# v7-flex2811_32x.net
KiCad netlist of a schematic drawn in EAGLE
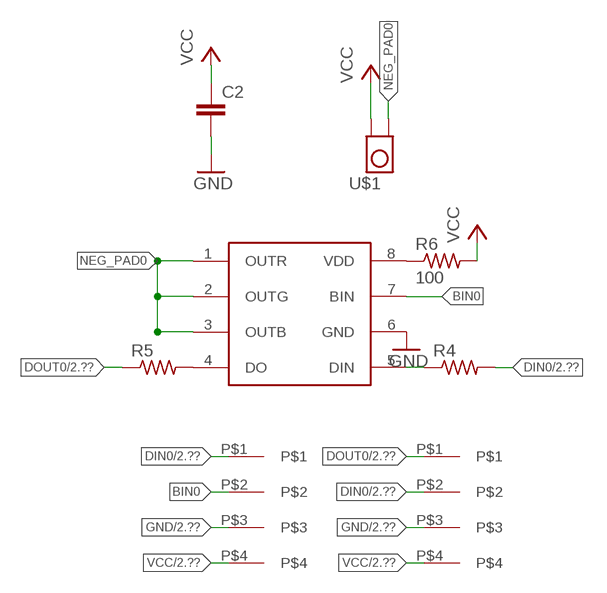
[diagram p0: schematic, sheet 1]
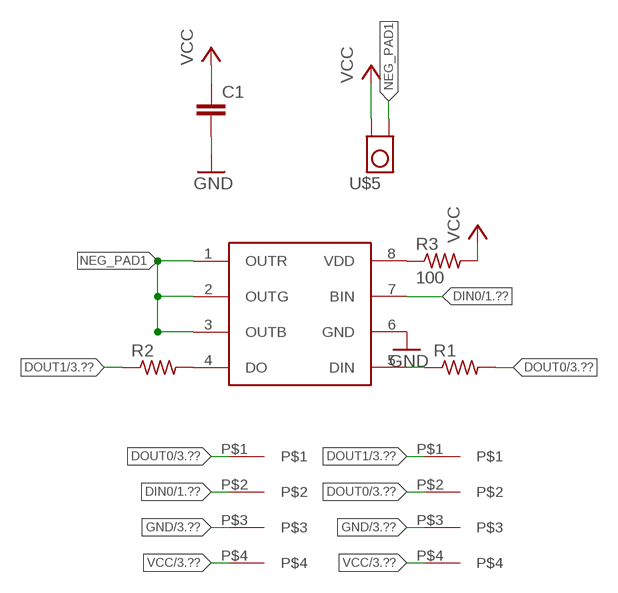
[diagram p1: schematic, sheet 2]
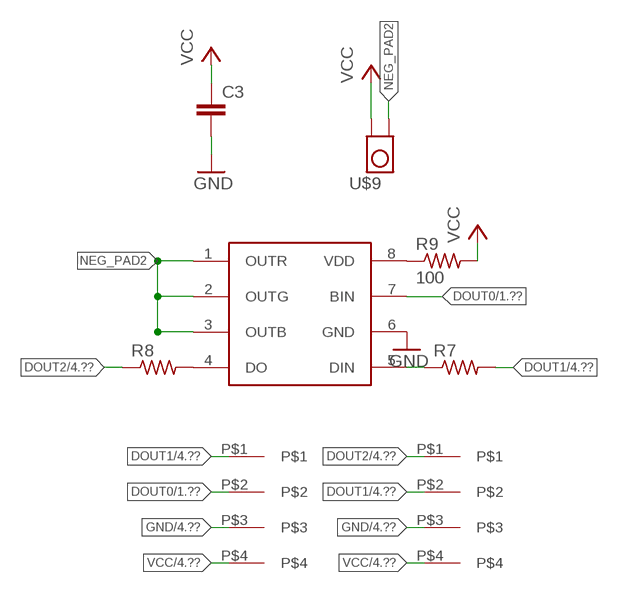
[diagram p2: schematic, sheet 3]
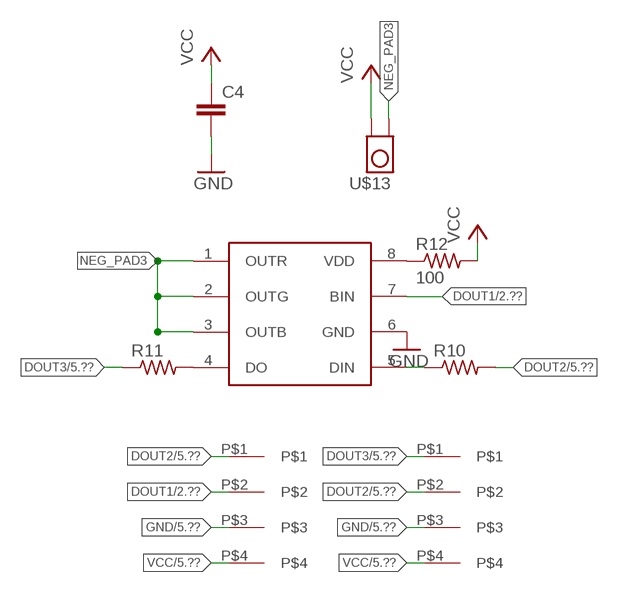
[diagram p3: schematic, sheet 4]
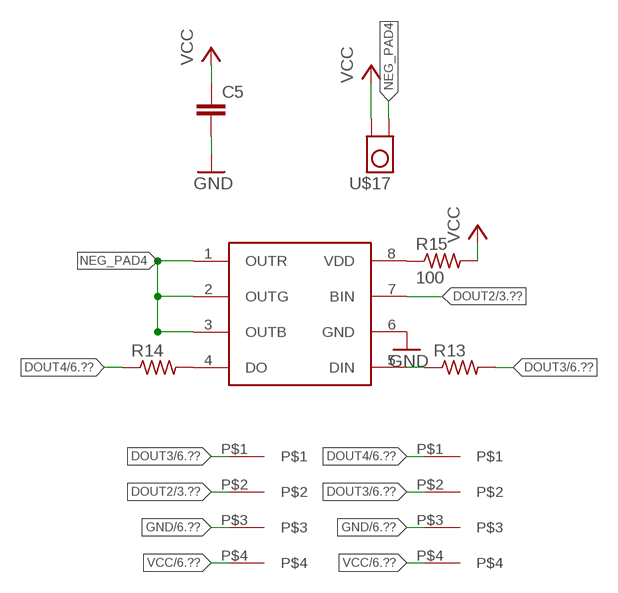
[diagram p4: schematic, sheet 5]
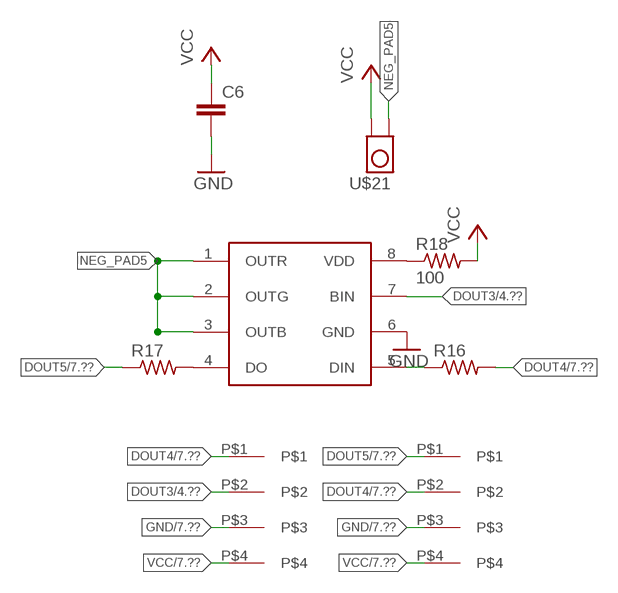
[diagram p5: schematic, sheet 6]
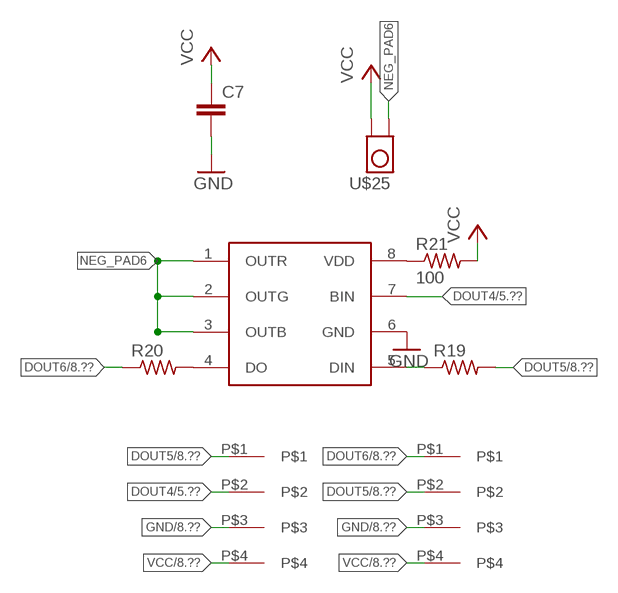
[diagram p6: schematic, sheet 7]
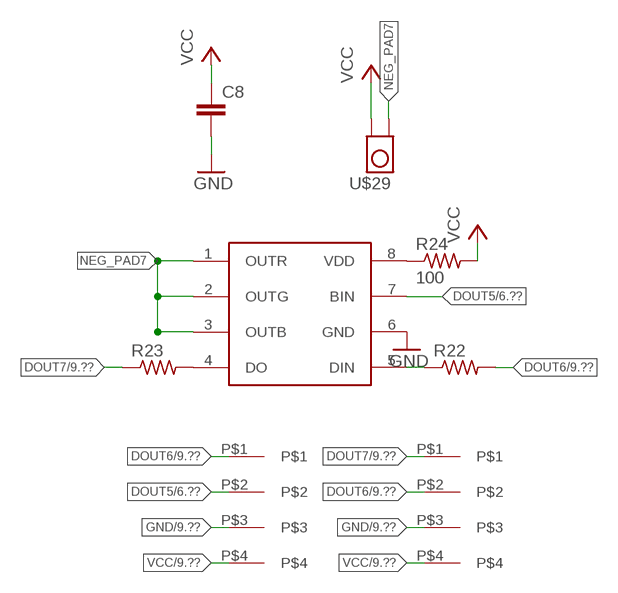
[diagram p7: schematic, sheet 8]
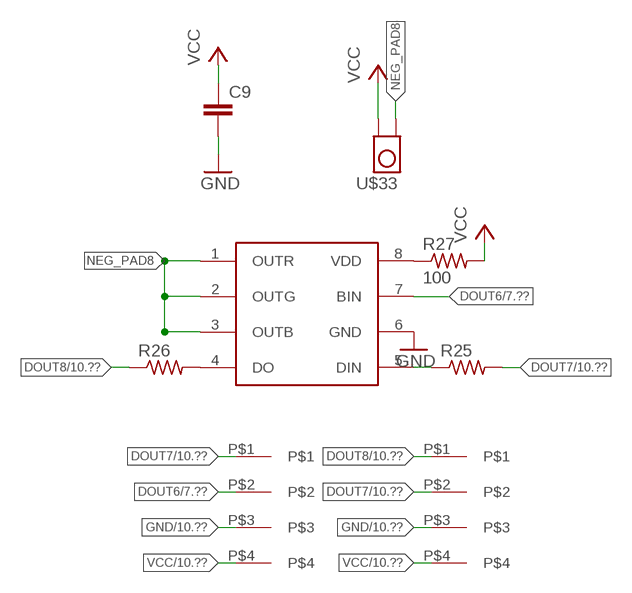
[diagram p8: schematic, sheet 9]
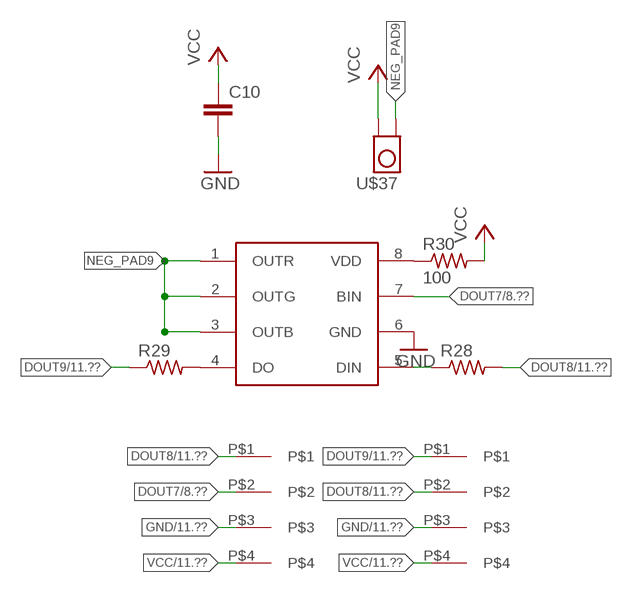
[diagram p9: schematic, sheet 10]
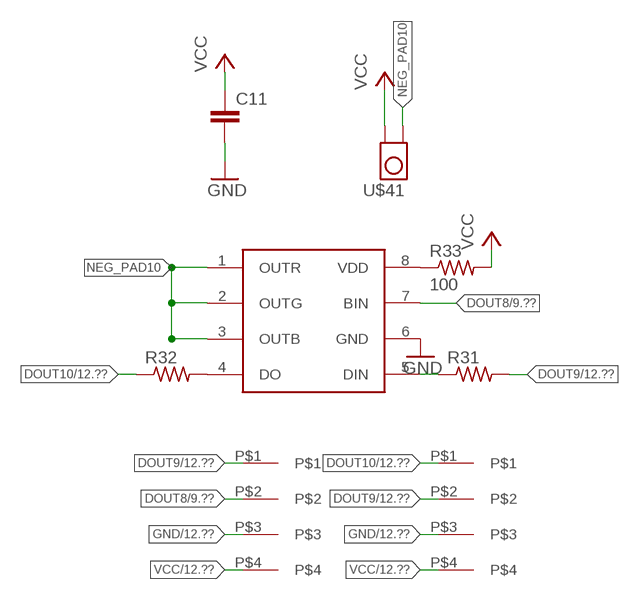
[diagram p10: schematic, sheet 11]
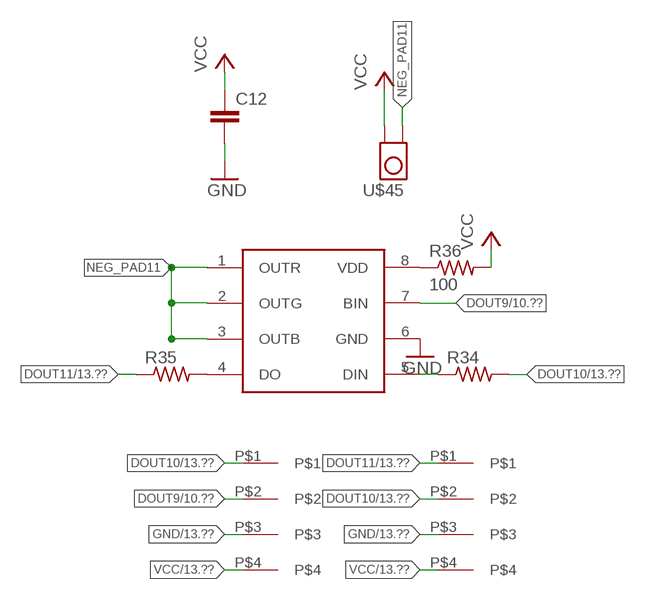
[diagram p11: schematic, sheet 12]
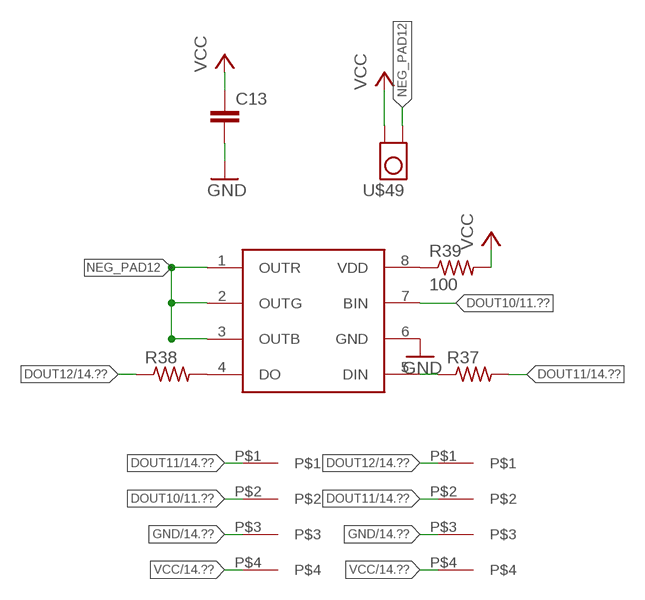
[diagram p12: schematic, sheet 13]
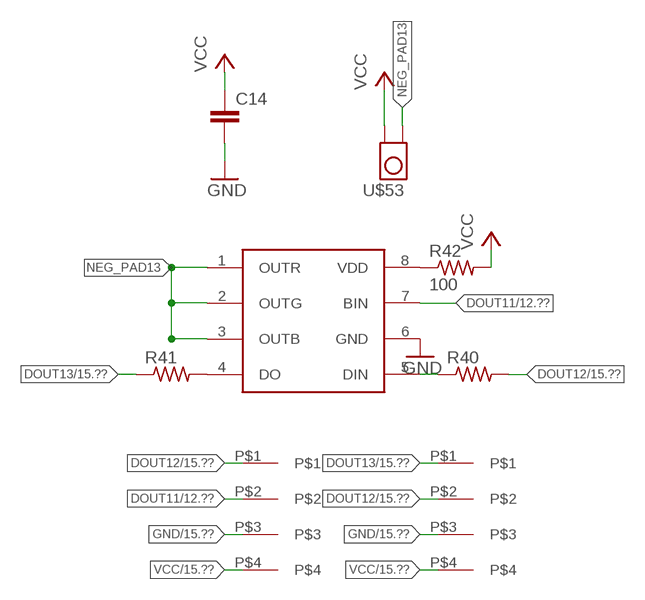
[diagram p13: schematic, sheet 14]
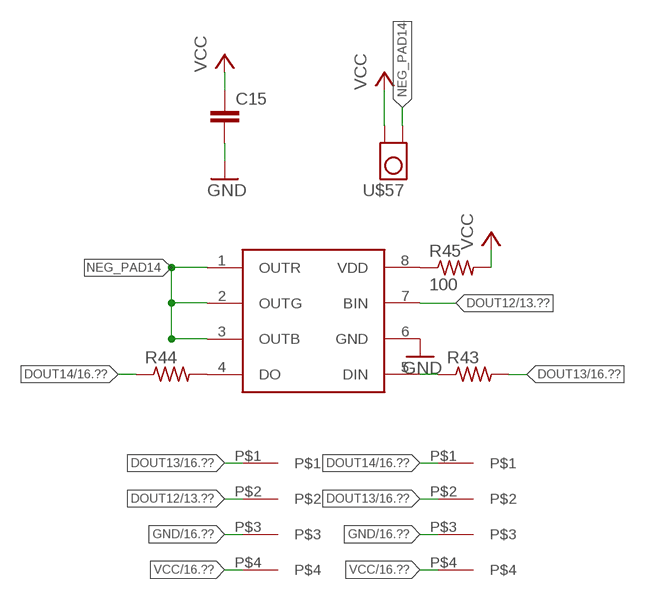
[diagram p14: schematic, sheet 15]
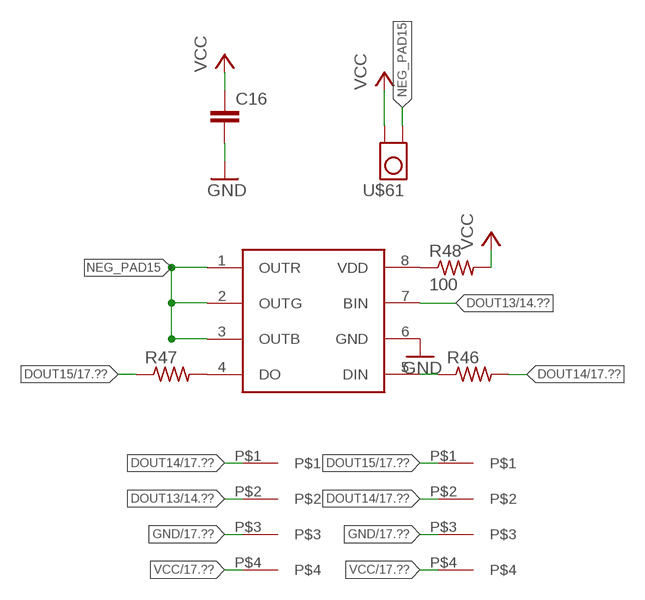
[diagram p15: schematic, sheet 16]
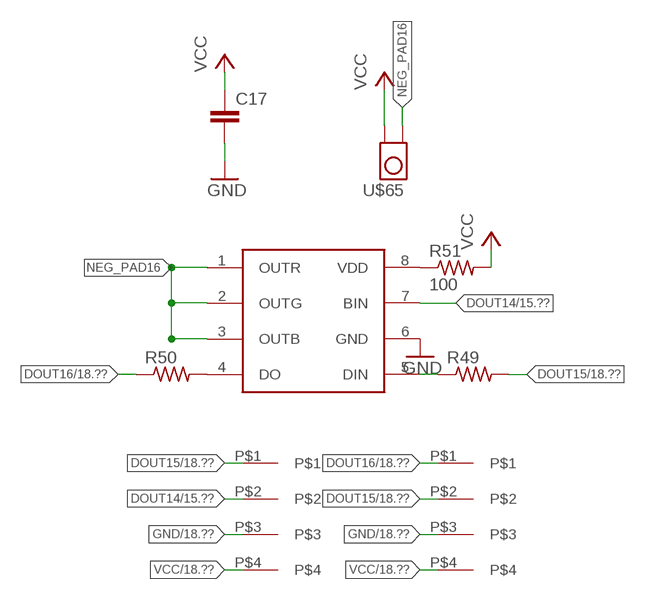
[diagram p16: schematic, sheet 17]
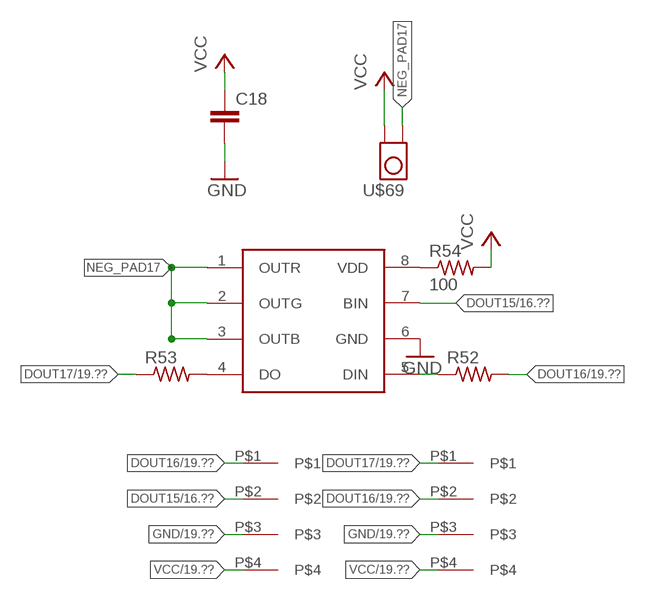
[diagram p17: schematic, sheet 18]
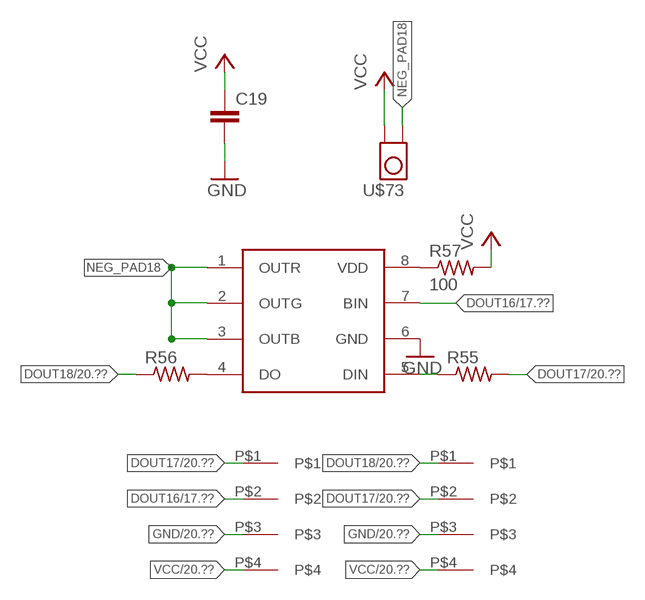
[diagram p18: schematic, sheet 19]
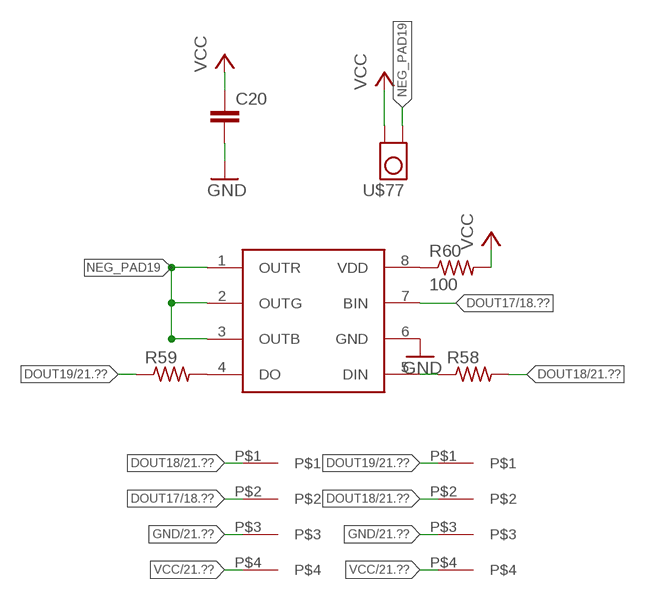
[diagram p19: schematic, sheet 20]
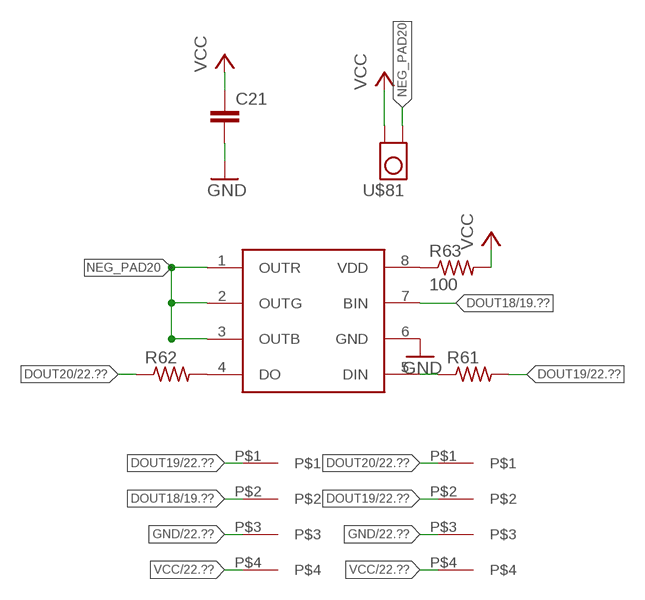
[diagram p20: schematic, sheet 21]
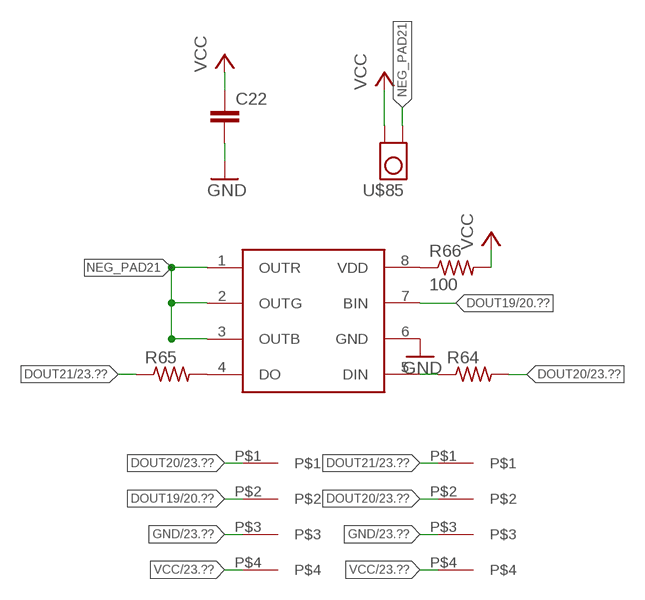
[diagram p21: schematic, sheet 22]
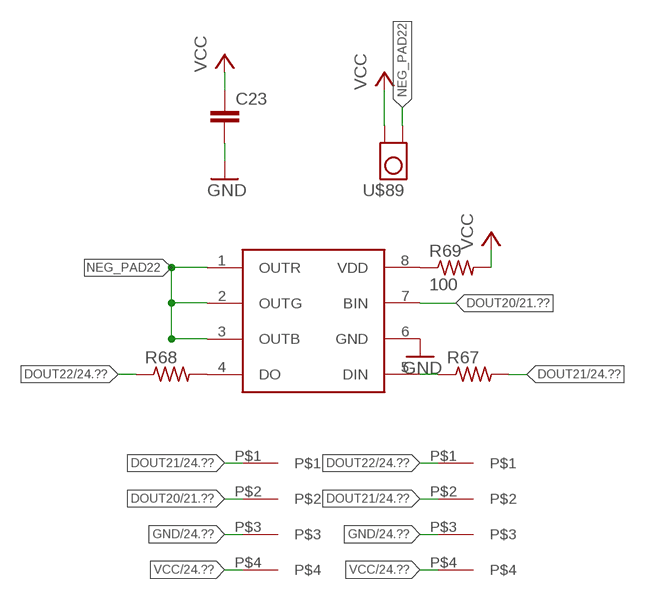
[diagram p22: schematic, sheet 23]
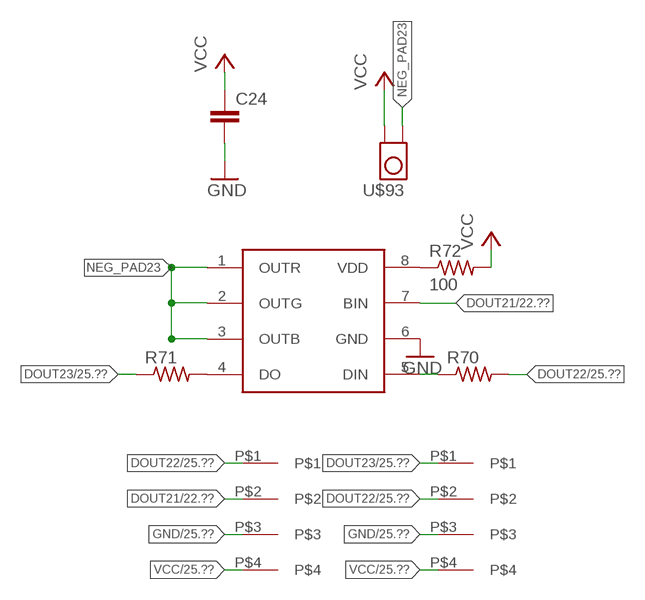
[diagram p23: schematic, sheet 24]
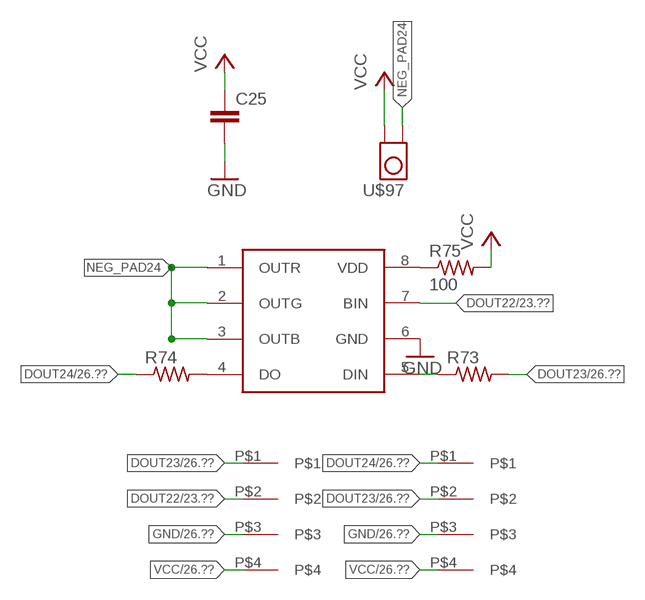
[diagram p24: schematic, sheet 25]
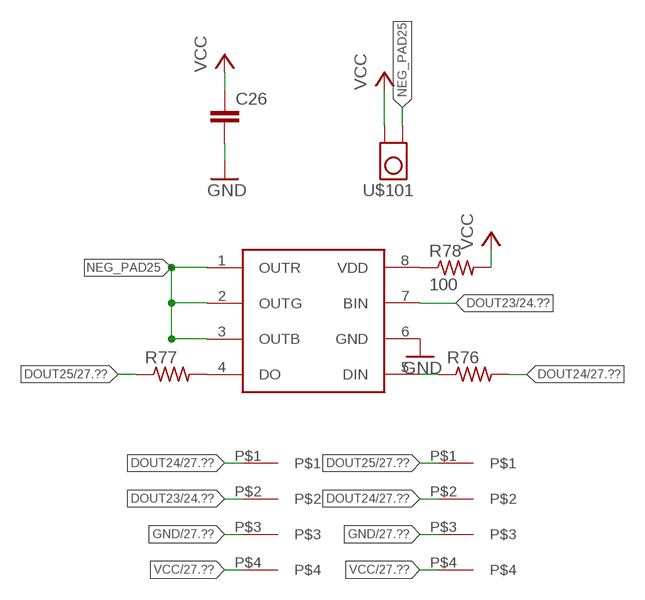
[diagram p25: schematic, sheet 26]
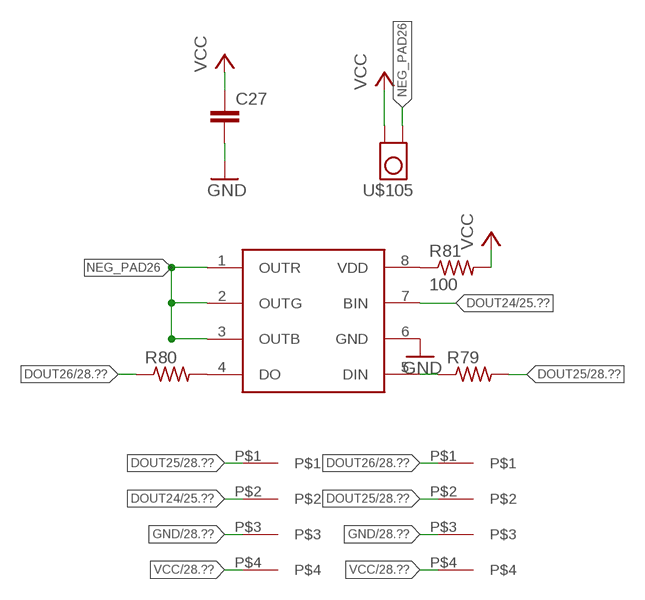
[diagram p26: schematic, sheet 27]
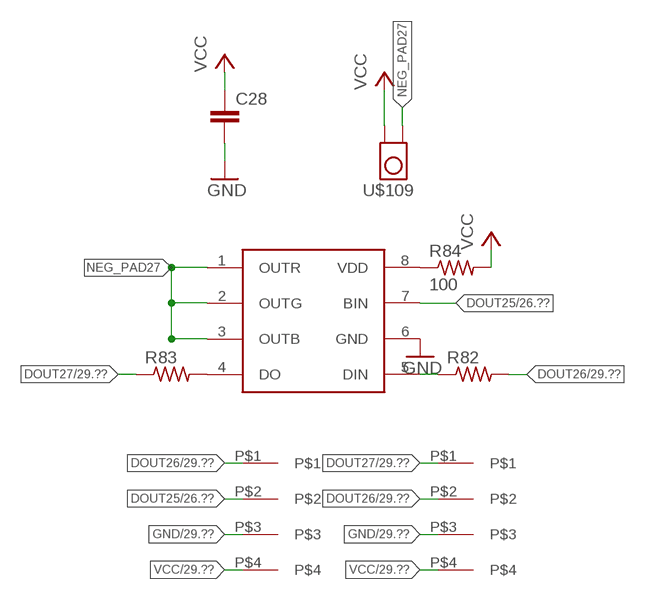
[diagram p27: schematic, sheet 28]
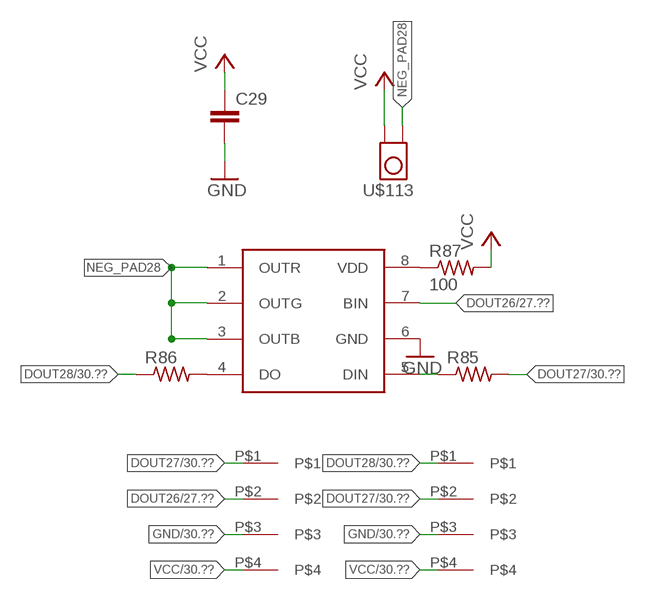
[diagram p28: schematic, sheet 29]
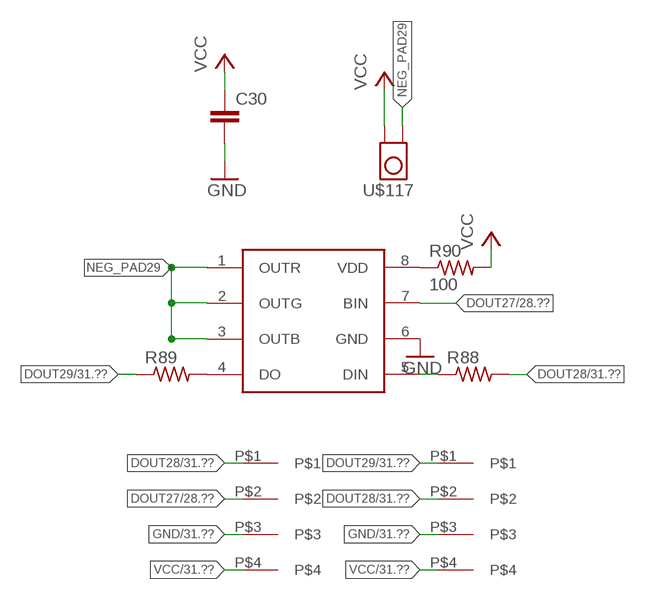
[diagram p29: schematic, sheet 30]
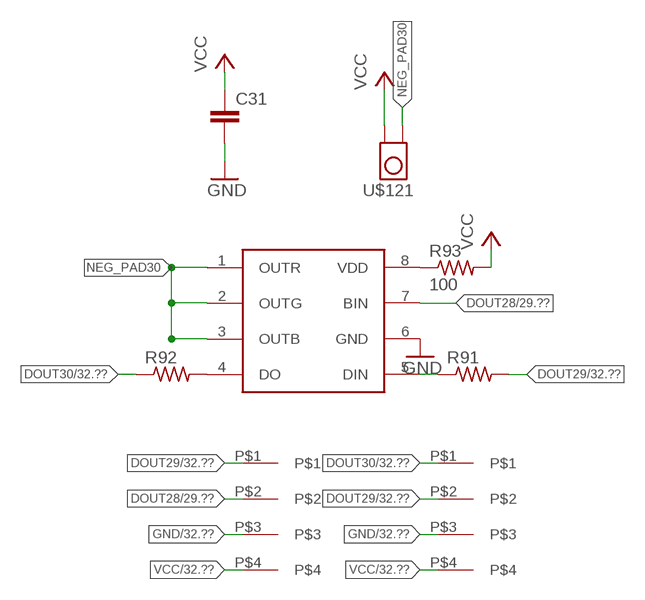
[diagram p30: schematic, sheet 31]
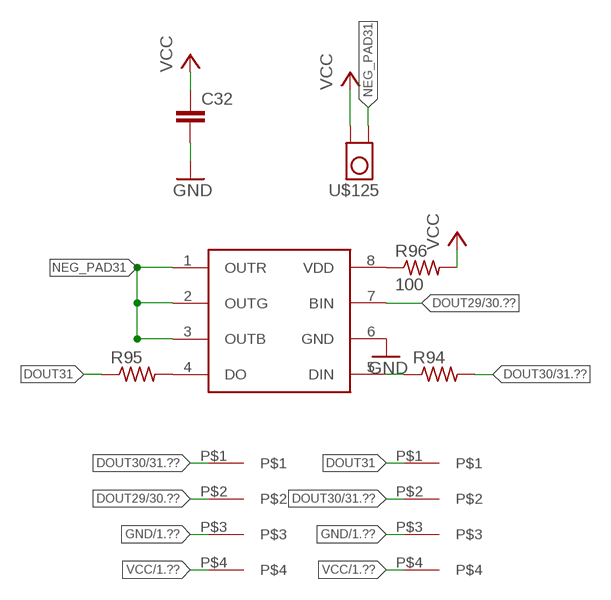
[diagram p31: schematic, sheet 32]

(export (version "E")
  (design (tool "Eeschema 10.0.6"))
  (components
    (comp (ref "C19")
      (value "C-EUC0201")
      (footprint "eagle-import:C0201")
      (libsource (lib "eagle-import") (part "C-EUC0201"))
    )
    (comp (ref "R55")
      (value "R-US_R0201")
      (footprint "eagle-import:R0201")
      (libsource (lib "eagle-import") (part "R-US_R0201"))
    )
    (comp (ref "R56")
      (value "R-US_R0201")
      (footprint "eagle-import:R0201")
      (libsource (lib "eagle-import") (part "R-US_R0201"))
    )
    (comp (ref "R57")
      (value "100")
      (footprint "eagle-import:R0201")
      (libsource (lib "eagle-import") (part "R-US_R0201"))
    )
    (comp (ref "U$73")
      (value "TP_4MM_MED_PAD")
      (footprint "eagle-import:TP_4MM_MED_PAD")
      (libsource (lib "eagle-import") (part "TP_4MM_MED_PAD"))
    )
    (comp (ref "U$75")
      (value "4PAD")
      (footprint "eagle-import:4PAD")
      (libsource (lib "eagle-import") (part "4PAD"))
    )
    (comp (ref "U$76")
      (value "4PAD")
      (footprint "eagle-import:4PAD")
      (libsource (lib "eagle-import") (part "4PAD"))
    )
    (comp (ref "U19")
      (value "WS2818")
      (footprint "eagle-import:SO08")
      (libsource (lib "eagle-import") (part "WS2818"))
    )
    (comp (ref "C20")
      (value "C-EUC0201")
      (footprint "eagle-import:C0201")
      (libsource (lib "eagle-import") (part "C-EUC0201"))
    )
    (comp (ref "R58")
      (value "R-US_R0201")
      (footprint "eagle-import:R0201")
      (libsource (lib "eagle-import") (part "R-US_R0201"))
    )
    (comp (ref "R59")
      (value "R-US_R0201")
      (footprint "eagle-import:R0201")
      (libsource (lib "eagle-import") (part "R-US_R0201"))
    )
    (comp (ref "R60")
      (value "100")
      (footprint "eagle-import:R0201")
      (libsource (lib "eagle-import") (part "R-US_R0201"))
    )
    (comp (ref "U$77")
      (value "TP_4MM_MED_PAD")
      (footprint "eagle-import:TP_4MM_MED_PAD")
      (libsource (lib "eagle-import") (part "TP_4MM_MED_PAD"))
    )
    (comp (ref "U$79")
      (value "4PAD")
      (footprint "eagle-import:4PAD")
      (libsource (lib "eagle-import") (part "4PAD"))
    )
    (comp (ref "U$80")
      (value "4PAD")
      (footprint "eagle-import:4PAD")
      (libsource (lib "eagle-import") (part "4PAD"))
    )
    (comp (ref "U20")
      (value "WS2818")
      (footprint "eagle-import:SO08")
      (libsource (lib "eagle-import") (part "WS2818"))
    )
    (comp (ref "C11")
      (value "C-EUC0201")
      (footprint "eagle-import:C0201")
      (libsource (lib "eagle-import") (part "C-EUC0201"))
    )
    (comp (ref "R31")
      (value "R-US_R0201")
      (footprint "eagle-import:R0201")
      (libsource (lib "eagle-import") (part "R-US_R0201"))
    )
    (comp (ref "R32")
      (value "R-US_R0201")
      (footprint "eagle-import:R0201")
      (libsource (lib "eagle-import") (part "R-US_R0201"))
    )
    (comp (ref "R33")
      (value "100")
      (footprint "eagle-import:R0201")
      (libsource (lib "eagle-import") (part "R-US_R0201"))
    )
    (comp (ref "U$41")
      (value "TP_4MM_MED_PAD")
      (footprint "eagle-import:TP_4MM_MED_PAD")
      (libsource (lib "eagle-import") (part "TP_4MM_MED_PAD"))
    )
    (comp (ref "U$43")
      (value "4PAD")
      (footprint "eagle-import:4PAD")
      (libsource (lib "eagle-import") (part "4PAD"))
    )
    (comp (ref "U$44")
      (value "4PAD")
      (footprint "eagle-import:4PAD")
      (libsource (lib "eagle-import") (part "4PAD"))
    )
    (comp (ref "U11")
      (value "WS2818")
      (footprint "eagle-import:SO08")
      (libsource (lib "eagle-import") (part "WS2818"))
    )
    (comp (ref "C17")
      (value "C-EUC0201")
      (footprint "eagle-import:C0201")
      (libsource (lib "eagle-import") (part "C-EUC0201"))
    )
    (comp (ref "R49")
      (value "R-US_R0201")
      (footprint "eagle-import:R0201")
      (libsource (lib "eagle-import") (part "R-US_R0201"))
    )
    (comp (ref "R50")
      (value "R-US_R0201")
      (footprint "eagle-import:R0201")
      (libsource (lib "eagle-import") (part "R-US_R0201"))
    )
    (comp (ref "R51")
      (value "100")
      (footprint "eagle-import:R0201")
      (libsource (lib "eagle-import") (part "R-US_R0201"))
    )
    (comp (ref "U$65")
      (value "TP_4MM_MED_PAD")
      (footprint "eagle-import:TP_4MM_MED_PAD")
      (libsource (lib "eagle-import") (part "TP_4MM_MED_PAD"))
    )
    (comp (ref "U$67")
      (value "4PAD")
      (footprint "eagle-import:4PAD")
      (libsource (lib "eagle-import") (part "4PAD"))
    )
    (comp (ref "U$68")
      (value "4PAD")
      (footprint "eagle-import:4PAD")
      (libsource (lib "eagle-import") (part "4PAD"))
    )
    (comp (ref "U17")
      (value "WS2818")
      (footprint "eagle-import:SO08")
      (libsource (lib "eagle-import") (part "WS2818"))
    )
    (comp (ref "C8")
      (value "C-EUC0201")
      (footprint "eagle-import:C0201")
      (libsource (lib "eagle-import") (part "C-EUC0201"))
    )
    (comp (ref "R22")
      (value "R-US_R0201")
      (footprint "eagle-import:R0201")
      (libsource (lib "eagle-import") (part "R-US_R0201"))
    )
    (comp (ref "R23")
      (value "R-US_R0201")
      (footprint "eagle-import:R0201")
      (libsource (lib "eagle-import") (part "R-US_R0201"))
    )
    (comp (ref "R24")
      (value "100")
      (footprint "eagle-import:R0201")
      (libsource (lib "eagle-import") (part "R-US_R0201"))
    )
    (comp (ref "U$29")
      (value "TP_4MM_MED_PAD")
      (footprint "eagle-import:TP_4MM_MED_PAD")
      (libsource (lib "eagle-import") (part "TP_4MM_MED_PAD"))
    )
    (comp (ref "U$31")
      (value "4PAD")
      (footprint "eagle-import:4PAD")
      (libsource (lib "eagle-import") (part "4PAD"))
    )
    (comp (ref "U$32")
      (value "4PAD")
      (footprint "eagle-import:4PAD")
      (libsource (lib "eagle-import") (part "4PAD"))
    )
    (comp (ref "U8")
      (value "WS2818")
      (footprint "eagle-import:SO08")
      (libsource (lib "eagle-import") (part "WS2818"))
    )
    (comp (ref "C21")
      (value "C-EUC0201")
      (footprint "eagle-import:C0201")
      (libsource (lib "eagle-import") (part "C-EUC0201"))
    )
    (comp (ref "R61")
      (value "R-US_R0201")
      (footprint "eagle-import:R0201")
      (libsource (lib "eagle-import") (part "R-US_R0201"))
    )
    (comp (ref "R62")
      (value "R-US_R0201")
      (footprint "eagle-import:R0201")
      (libsource (lib "eagle-import") (part "R-US_R0201"))
    )
    (comp (ref "R63")
      (value "100")
      (footprint "eagle-import:R0201")
      (libsource (lib "eagle-import") (part "R-US_R0201"))
    )
    (comp (ref "U$81")
      (value "TP_4MM_MED_PAD")
      (footprint "eagle-import:TP_4MM_MED_PAD")
      (libsource (lib "eagle-import") (part "TP_4MM_MED_PAD"))
    )
    (comp (ref "U$83")
      (value "4PAD")
      (footprint "eagle-import:4PAD")
      (libsource (lib "eagle-import") (part "4PAD"))
    )
    (comp (ref "U$84")
      (value "4PAD")
      (footprint "eagle-import:4PAD")
      (libsource (lib "eagle-import") (part "4PAD"))
    )
    (comp (ref "U21")
      (value "WS2818")
      (footprint "eagle-import:SO08")
      (libsource (lib "eagle-import") (part "WS2818"))
    )
    (comp (ref "C3")
      (value "C-EUC0201")
      (footprint "eagle-import:C0201")
      (libsource (lib "eagle-import") (part "C-EUC0201"))
    )
    (comp (ref "R7")
      (value "R-US_R0201")
      (footprint "eagle-import:R0201")
      (libsource (lib "eagle-import") (part "R-US_R0201"))
    )
    (comp (ref "R8")
      (value "R-US_R0201")
      (footprint "eagle-import:R0201")
      (libsource (lib "eagle-import") (part "R-US_R0201"))
    )
    (comp (ref "R9")
      (value "100")
      (footprint "eagle-import:R0201")
      (libsource (lib "eagle-import") (part "R-US_R0201"))
    )
    (comp (ref "U$9")
      (value "TP_4MM_MED_PAD")
      (footprint "eagle-import:TP_4MM_MED_PAD")
      (libsource (lib "eagle-import") (part "TP_4MM_MED_PAD"))
    )
    (comp (ref "U$11")
      (value "4PAD")
      (footprint "eagle-import:4PAD")
      (libsource (lib "eagle-import") (part "4PAD"))
    )
    (comp (ref "U$12")
      (value "4PAD")
      (footprint "eagle-import:4PAD")
      (libsource (lib "eagle-import") (part "4PAD"))
    )
    (comp (ref "U3")
      (value "WS2818")
      (footprint "eagle-import:SO08")
      (libsource (lib "eagle-import") (part "WS2818"))
    )
    (comp (ref "C2")
      (value "C-EUC0201")
      (footprint "eagle-import:C0201")
      (libsource (lib "eagle-import") (part "C-EUC0201"))
    )
    (comp (ref "R4")
      (value "R-US_R0201")
      (footprint "eagle-import:R0201")
      (libsource (lib "eagle-import") (part "R-US_R0201"))
    )
    (comp (ref "R5")
      (value "R-US_R0201")
      (footprint "eagle-import:R0201")
      (libsource (lib "eagle-import") (part "R-US_R0201"))
    )
    (comp (ref "R6")
      (value "100")
      (footprint "eagle-import:R0201")
      (libsource (lib "eagle-import") (part "R-US_R0201"))
    )
    (comp (ref "U$1")
      (value "TP_4MM_MED_PAD")
      (footprint "eagle-import:TP_4MM_MED_PAD")
      (libsource (lib "eagle-import") (part "TP_4MM_MED_PAD"))
    )
    (comp (ref "U$3")
      (value "4PAD")
      (footprint "eagle-import:4PAD")
      (libsource (lib "eagle-import") (part "4PAD"))
    )
    (comp (ref "U$4")
      (value "4PAD")
      (footprint "eagle-import:4PAD")
      (libsource (lib "eagle-import") (part "4PAD"))
    )
    (comp (ref "U1")
      (value "WS2818")
      (footprint "eagle-import:SO08")
      (libsource (lib "eagle-import") (part "WS2818"))
    )
    (comp (ref "C31")
      (value "C-EUC0201")
      (footprint "eagle-import:C0201")
      (libsource (lib "eagle-import") (part "C-EUC0201"))
    )
    (comp (ref "R91")
      (value "R-US_R0201")
      (footprint "eagle-import:R0201")
      (libsource (lib "eagle-import") (part "R-US_R0201"))
    )
    (comp (ref "R92")
      (value "R-US_R0201")
      (footprint "eagle-import:R0201")
      (libsource (lib "eagle-import") (part "R-US_R0201"))
    )
    (comp (ref "R93")
      (value "100")
      (footprint "eagle-import:R0201")
      (libsource (lib "eagle-import") (part "R-US_R0201"))
    )
    (comp (ref "U$121")
      (value "TP_4MM_MED_PAD")
      (footprint "eagle-import:TP_4MM_MED_PAD")
      (libsource (lib "eagle-import") (part "TP_4MM_MED_PAD"))
    )
    (comp (ref "U$123")
      (value "4PAD")
      (footprint "eagle-import:4PAD")
      (libsource (lib "eagle-import") (part "4PAD"))
    )
    (comp (ref "U$124")
      (value "4PAD")
      (footprint "eagle-import:4PAD")
      (libsource (lib "eagle-import") (part "4PAD"))
    )
    (comp (ref "U31")
      (value "WS2818")
      (footprint "eagle-import:SO08")
      (libsource (lib "eagle-import") (part "WS2818"))
    )
    (comp (ref "C29")
      (value "C-EUC0201")
      (footprint "eagle-import:C0201")
      (libsource (lib "eagle-import") (part "C-EUC0201"))
    )
    (comp (ref "R85")
      (value "R-US_R0201")
      (footprint "eagle-import:R0201")
      (libsource (lib "eagle-import") (part "R-US_R0201"))
    )
    (comp (ref "R86")
      (value "R-US_R0201")
      (footprint "eagle-import:R0201")
      (libsource (lib "eagle-import") (part "R-US_R0201"))
    )
    (comp (ref "R87")
      (value "100")
      (footprint "eagle-import:R0201")
      (libsource (lib "eagle-import") (part "R-US_R0201"))
    )
    (comp (ref "U$113")
      (value "TP_4MM_MED_PAD")
      (footprint "eagle-import:TP_4MM_MED_PAD")
      (libsource (lib "eagle-import") (part "TP_4MM_MED_PAD"))
    )
    (comp (ref "U$115")
      (value "4PAD")
      (footprint "eagle-import:4PAD")
      (libsource (lib "eagle-import") (part "4PAD"))
    )
    (comp (ref "U$116")
      (value "4PAD")
      (footprint "eagle-import:4PAD")
      (libsource (lib "eagle-import") (part "4PAD"))
    )
    (comp (ref "U29")
      (value "WS2818")
      (footprint "eagle-import:SO08")
      (libsource (lib "eagle-import") (part "WS2818"))
    )
    (comp (ref "C15")
      (value "C-EUC0201")
      (footprint "eagle-import:C0201")
      (libsource (lib "eagle-import") (part "C-EUC0201"))
    )
    (comp (ref "R43")
      (value "R-US_R0201")
      (footprint "eagle-import:R0201")
      (libsource (lib "eagle-import") (part "R-US_R0201"))
    )
    (comp (ref "R44")
      (value "R-US_R0201")
      (footprint "eagle-import:R0201")
      (libsource (lib "eagle-import") (part "R-US_R0201"))
    )
    (comp (ref "R45")
      (value "100")
      (footprint "eagle-import:R0201")
      (libsource (lib "eagle-import") (part "R-US_R0201"))
    )
    (comp (ref "U$57")
      (value "TP_4MM_MED_PAD")
      (footprint "eagle-import:TP_4MM_MED_PAD")
      (libsource (lib "eagle-import") (part "TP_4MM_MED_PAD"))
    )
    (comp (ref "U$59")
      (value "4PAD")
      (footprint "eagle-import:4PAD")
      (libsource (lib "eagle-import") (part "4PAD"))
    )
    (comp (ref "U$60")
      (value "4PAD")
      (footprint "eagle-import:4PAD")
      (libsource (lib "eagle-import") (part "4PAD"))
    )
    (comp (ref "U15")
      (value "WS2818")
      (footprint "eagle-import:SO08")
      (libsource (lib "eagle-import") (part "WS2818"))
    )
    (comp (ref "C25")
      (value "C-EUC0201")
      (footprint "eagle-import:C0201")
      (libsource (lib "eagle-import") (part "C-EUC0201"))
    )
    (comp (ref "R73")
      (value "R-US_R0201")
      (footprint "eagle-import:R0201")
      (libsource (lib "eagle-import") (part "R-US_R0201"))
    )
    (comp (ref "R74")
      (value "R-US_R0201")
      (footprint "eagle-import:R0201")
      (libsource (lib "eagle-import") (part "R-US_R0201"))
    )
    (comp (ref "R75")
      (value "100")
      (footprint "eagle-import:R0201")
      (libsource (lib "eagle-import") (part "R-US_R0201"))
    )
    (comp (ref "U$97")
      (value "TP_4MM_MED_PAD")
      (footprint "eagle-import:TP_4MM_MED_PAD")
      (libsource (lib "eagle-import") (part "TP_4MM_MED_PAD"))
    )
    (comp (ref "U$99")
      (value "4PAD")
      (footprint "eagle-import:4PAD")
      (libsource (lib "eagle-import") (part "4PAD"))
    )
    (comp (ref "U$100")
      (value "4PAD")
      (footprint "eagle-import:4PAD")
      (libsource (lib "eagle-import") (part "4PAD"))
    )
    (comp (ref "U25")
      (value "WS2818")
      (footprint "eagle-import:SO08")
      (libsource (lib "eagle-import") (part "WS2818"))
    )
    (comp (ref "C1")
      (value "C-EUC0201")
      (footprint "eagle-import:C0201")
      (libsource (lib "eagle-import") (part "C-EUC0201"))
    )
    (comp (ref "R1")
      (value "R-US_R0201")
      (footprint "eagle-import:R0201")
      (libsource (lib "eagle-import") (part "R-US_R0201"))
    )
    (comp (ref "R2")
      (value "R-US_R0201")
      (footprint "eagle-import:R0201")
      (libsource (lib "eagle-import") (part "R-US_R0201"))
    )
    (comp (ref "R3")
      (value "100")
      (footprint "eagle-import:R0201")
      (libsource (lib "eagle-import") (part "R-US_R0201"))
    )
    (comp (ref "U$5")
      (value "TP_4MM_MED_PAD")
      (footprint "eagle-import:TP_4MM_MED_PAD")
      (libsource (lib "eagle-import") (part "TP_4MM_MED_PAD"))
    )
    (comp (ref "U$7")
      (value "4PAD")
      (footprint "eagle-import:4PAD")
      (libsource (lib "eagle-import") (part "4PAD"))
    )
    (comp (ref "U$8")
      (value "4PAD")
      (footprint "eagle-import:4PAD")
      (libsource (lib "eagle-import") (part "4PAD"))
    )
    (comp (ref "U2")
      (value "WS2818")
      (footprint "eagle-import:SO08")
      (libsource (lib "eagle-import") (part "WS2818"))
    )
    (comp (ref "C22")
      (value "C-EUC0201")
      (footprint "eagle-import:C0201")
      (libsource (lib "eagle-import") (part "C-EUC0201"))
    )
    (comp (ref "R64")
      (value "R-US_R0201")
      (footprint "eagle-import:R0201")
      (libsource (lib "eagle-import") (part "R-US_R0201"))
    )
    (comp (ref "R65")
      (value "R-US_R0201")
      (footprint "eagle-import:R0201")
      (libsource (lib "eagle-import") (part "R-US_R0201"))
    )
    (comp (ref "R66")
      (value "100")
      (footprint "eagle-import:R0201")
      (libsource (lib "eagle-import") (part "R-US_R0201"))
    )
    (comp (ref "U$85")
      (value "TP_4MM_MED_PAD")
      (footprint "eagle-import:TP_4MM_MED_PAD")
      (libsource (lib "eagle-import") (part "TP_4MM_MED_PAD"))
    )
    (comp (ref "U$87")
      (value "4PAD")
      (footprint "eagle-import:4PAD")
      (libsource (lib "eagle-import") (part "4PAD"))
    )
    (comp (ref "U$88")
      (value "4PAD")
      (footprint "eagle-import:4PAD")
      (libsource (lib "eagle-import") (part "4PAD"))
    )
    (comp (ref "U22")
      (value "WS2818")
      (footprint "eagle-import:SO08")
      (libsource (lib "eagle-import") (part "WS2818"))
    )
    (comp (ref "C26")
      (value "C-EUC0201")
      (footprint "eagle-import:C0201")
      (libsource (lib "eagle-import") (part "C-EUC0201"))
    )
    (comp (ref "R76")
      (value "R-US_R0201")
      (footprint "eagle-import:R0201")
      (libsource (lib "eagle-import") (part "R-US_R0201"))
    )
    (comp (ref "R77")
      (value "R-US_R0201")
      (footprint "eagle-import:R0201")
      (libsource (lib "eagle-import") (part "R-US_R0201"))
    )
    (comp (ref "R78")
      (value "100")
      (footprint "eagle-import:R0201")
      (libsource (lib "eagle-import") (part "R-US_R0201"))
    )
    (comp (ref "U$101")
      (value "TP_4MM_MED_PAD")
      (footprint "eagle-import:TP_4MM_MED_PAD")
      (libsource (lib "eagle-import") (part "TP_4MM_MED_PAD"))
    )
    (comp (ref "U$103")
      (value "4PAD")
      (footprint "eagle-import:4PAD")
      (libsource (lib "eagle-import") (part "4PAD"))
    )
    (comp (ref "U$104")
      (value "4PAD")
      (footprint "eagle-import:4PAD")
      (libsource (lib "eagle-import") (part "4PAD"))
    )
    (comp (ref "U26")
      (value "WS2818")
      (footprint "eagle-import:SO08")
      (libsource (lib "eagle-import") (part "WS2818"))
    )
    (comp (ref "C14")
      (value "C-EUC0201")
      (footprint "eagle-import:C0201")
      (libsource (lib "eagle-import") (part "C-EUC0201"))
    )
    (comp (ref "R40")
      (value "R-US_R0201")
      (footprint "eagle-import:R0201")
      (libsource (lib "eagle-import") (part "R-US_R0201"))
    )
    (comp (ref "R41")
      (value "R-US_R0201")
      (footprint "eagle-import:R0201")
      (libsource (lib "eagle-import") (part "R-US_R0201"))
    )
    (comp (ref "R42")
      (value "100")
      (footprint "eagle-import:R0201")
      (libsource (lib "eagle-import") (part "R-US_R0201"))
    )
    (comp (ref "U$53")
      (value "TP_4MM_MED_PAD")
      (footprint "eagle-import:TP_4MM_MED_PAD")
      (libsource (lib "eagle-import") (part "TP_4MM_MED_PAD"))
    )
    (comp (ref "U$55")
      (value "4PAD")
      (footprint "eagle-import:4PAD")
      (libsource (lib "eagle-import") (part "4PAD"))
    )
    (comp (ref "U$56")
      (value "4PAD")
      (footprint "eagle-import:4PAD")
      (libsource (lib "eagle-import") (part "4PAD"))
    )
    (comp (ref "U14")
      (value "WS2818")
      (footprint "eagle-import:SO08")
      (libsource (lib "eagle-import") (part "WS2818"))
    )
    (comp (ref "C30")
      (value "C-EUC0201")
      (footprint "eagle-import:C0201")
      (libsource (lib "eagle-import") (part "C-EUC0201"))
    )
    (comp (ref "R88")
      (value "R-US_R0201")
      (footprint "eagle-import:R0201")
      (libsource (lib "eagle-import") (part "R-US_R0201"))
    )
    (comp (ref "R89")
      (value "R-US_R0201")
      (footprint "eagle-import:R0201")
      (libsource (lib "eagle-import") (part "R-US_R0201"))
    )
    (comp (ref "R90")
      (value "100")
      (footprint "eagle-import:R0201")
      (libsource (lib "eagle-import") (part "R-US_R0201"))
    )
    (comp (ref "U$117")
      (value "TP_4MM_MED_PAD")
      (footprint "eagle-import:TP_4MM_MED_PAD")
      (libsource (lib "eagle-import") (part "TP_4MM_MED_PAD"))
    )
    (comp (ref "U$119")
      (value "4PAD")
      (footprint "eagle-import:4PAD")
      (libsource (lib "eagle-import") (part "4PAD"))
    )
    (comp (ref "U$120")
      (value "4PAD")
      (footprint "eagle-import:4PAD")
      (libsource (lib "eagle-import") (part "4PAD"))
    )
    (comp (ref "U30")
      (value "WS2818")
      (footprint "eagle-import:SO08")
      (libsource (lib "eagle-import") (part "WS2818"))
    )
    (comp (ref "C23")
      (value "C-EUC0201")
      (footprint "eagle-import:C0201")
      (libsource (lib "eagle-import") (part "C-EUC0201"))
    )
    (comp (ref "R67")
      (value "R-US_R0201")
      (footprint "eagle-import:R0201")
      (libsource (lib "eagle-import") (part "R-US_R0201"))
    )
    (comp (ref "R68")
      (value "R-US_R0201")
      (footprint "eagle-import:R0201")
      (libsource (lib "eagle-import") (part "R-US_R0201"))
    )
    (comp (ref "R69")
      (value "100")
      (footprint "eagle-import:R0201")
      (libsource (lib "eagle-import") (part "R-US_R0201"))
    )
    (comp (ref "U$89")
      (value "TP_4MM_MED_PAD")
      (footprint "eagle-import:TP_4MM_MED_PAD")
      (libsource (lib "eagle-import") (part "TP_4MM_MED_PAD"))
    )
    (comp (ref "U$91")
      (value "4PAD")
      (footprint "eagle-import:4PAD")
      (libsource (lib "eagle-import") (part "4PAD"))
    )
    (comp (ref "U$92")
      (value "4PAD")
      (footprint "eagle-import:4PAD")
      (libsource (lib "eagle-import") (part "4PAD"))
    )
    (comp (ref "U23")
      (value "WS2818")
      (footprint "eagle-import:SO08")
      (libsource (lib "eagle-import") (part "WS2818"))
    )
    (comp (ref "C5")
      (value "C-EUC0201")
      (footprint "eagle-import:C0201")
      (libsource (lib "eagle-import") (part "C-EUC0201"))
    )
    (comp (ref "R13")
      (value "R-US_R0201")
      (footprint "eagle-import:R0201")
      (libsource (lib "eagle-import") (part "R-US_R0201"))
    )
    (comp (ref "R14")
      (value "R-US_R0201")
      (footprint "eagle-import:R0201")
      (libsource (lib "eagle-import") (part "R-US_R0201"))
    )
    (comp (ref "R15")
      (value "100")
      (footprint "eagle-import:R0201")
      (libsource (lib "eagle-import") (part "R-US_R0201"))
    )
    (comp (ref "U$17")
      (value "TP_4MM_MED_PAD")
      (footprint "eagle-import:TP_4MM_MED_PAD")
      (libsource (lib "eagle-import") (part "TP_4MM_MED_PAD"))
    )
    (comp (ref "U$19")
      (value "4PAD")
      (footprint "eagle-import:4PAD")
      (libsource (lib "eagle-import") (part "4PAD"))
    )
    (comp (ref "U$20")
      (value "4PAD")
      (footprint "eagle-import:4PAD")
      (libsource (lib "eagle-import") (part "4PAD"))
    )
    (comp (ref "U5")
      (value "WS2818")
      (footprint "eagle-import:SO08")
      (libsource (lib "eagle-import") (part "WS2818"))
    )
    (comp (ref "C9")
      (value "C-EUC0201")
      (footprint "eagle-import:C0201")
      (libsource (lib "eagle-import") (part "C-EUC0201"))
    )
    (comp (ref "R25")
      (value "R-US_R0201")
      (footprint "eagle-import:R0201")
      (libsource (lib "eagle-import") (part "R-US_R0201"))
    )
    (comp (ref "R26")
      (value "R-US_R0201")
      (footprint "eagle-import:R0201")
      (libsource (lib "eagle-import") (part "R-US_R0201"))
    )
    (comp (ref "R27")
      (value "100")
      (footprint "eagle-import:R0201")
      (libsource (lib "eagle-import") (part "R-US_R0201"))
    )
    (comp (ref "U$33")
      (value "TP_4MM_MED_PAD")
      (footprint "eagle-import:TP_4MM_MED_PAD")
      (libsource (lib "eagle-import") (part "TP_4MM_MED_PAD"))
    )
    (comp (ref "U$35")
      (value "4PAD")
      (footprint "eagle-import:4PAD")
      (libsource (lib "eagle-import") (part "4PAD"))
    )
    (comp (ref "U$36")
      (value "4PAD")
      (footprint "eagle-import:4PAD")
      (libsource (lib "eagle-import") (part "4PAD"))
    )
    (comp (ref "U9")
      (value "WS2818")
      (footprint "eagle-import:SO08")
      (libsource (lib "eagle-import") (part "WS2818"))
    )
    (comp (ref "C7")
      (value "C-EUC0201")
      (footprint "eagle-import:C0201")
      (libsource (lib "eagle-import") (part "C-EUC0201"))
    )
    (comp (ref "R19")
      (value "R-US_R0201")
      (footprint "eagle-import:R0201")
      (libsource (lib "eagle-import") (part "R-US_R0201"))
    )
    (comp (ref "R20")
      (value "R-US_R0201")
      (footprint "eagle-import:R0201")
      (libsource (lib "eagle-import") (part "R-US_R0201"))
    )
    (comp (ref "R21")
      (value "100")
      (footprint "eagle-import:R0201")
      (libsource (lib "eagle-import") (part "R-US_R0201"))
    )
    (comp (ref "U$25")
      (value "TP_4MM_MED_PAD")
      (footprint "eagle-import:TP_4MM_MED_PAD")
      (libsource (lib "eagle-import") (part "TP_4MM_MED_PAD"))
    )
    (comp (ref "U$27")
      (value "4PAD")
      (footprint "eagle-import:4PAD")
      (libsource (lib "eagle-import") (part "4PAD"))
    )
    (comp (ref "U$28")
      (value "4PAD")
      (footprint "eagle-import:4PAD")
      (libsource (lib "eagle-import") (part "4PAD"))
    )
    (comp (ref "U7")
      (value "WS2818")
      (footprint "eagle-import:SO08")
      (libsource (lib "eagle-import") (part "WS2818"))
    )
    (comp (ref "C27")
      (value "C-EUC0201")
      (footprint "eagle-import:C0201")
      (libsource (lib "eagle-import") (part "C-EUC0201"))
    )
    (comp (ref "R79")
      (value "R-US_R0201")
      (footprint "eagle-import:R0201")
      (libsource (lib "eagle-import") (part "R-US_R0201"))
    )
    (comp (ref "R80")
      (value "R-US_R0201")
      (footprint "eagle-import:R0201")
      (libsource (lib "eagle-import") (part "R-US_R0201"))
    )
    (comp (ref "R81")
      (value "100")
      (footprint "eagle-import:R0201")
      (libsource (lib "eagle-import") (part "R-US_R0201"))
    )
    (comp (ref "U$105")
      (value "TP_4MM_MED_PAD")
      (footprint "eagle-import:TP_4MM_MED_PAD")
      (libsource (lib "eagle-import") (part "TP_4MM_MED_PAD"))
    )
    (comp (ref "U$107")
      (value "4PAD")
      (footprint "eagle-import:4PAD")
      (libsource (lib "eagle-import") (part "4PAD"))
    )
    (comp (ref "U$108")
      (value "4PAD")
      (footprint "eagle-import:4PAD")
      (libsource (lib "eagle-import") (part "4PAD"))
    )
    (comp (ref "U27")
      (value "WS2818")
      (footprint "eagle-import:SO08")
      (libsource (lib "eagle-import") (part "WS2818"))
    )
    (comp (ref "C4")
      (value "C-EUC0201")
      (footprint "eagle-import:C0201")
      (libsource (lib "eagle-import") (part "C-EUC0201"))
    )
    (comp (ref "R10")
      (value "R-US_R0201")
      (footprint "eagle-import:R0201")
      (libsource (lib "eagle-import") (part "R-US_R0201"))
    )
    (comp (ref "R11")
      (value "R-US_R0201")
      (footprint "eagle-import:R0201")
      (libsource (lib "eagle-import") (part "R-US_R0201"))
    )
    (comp (ref "R12")
      (value "100")
      (footprint "eagle-import:R0201")
      (libsource (lib "eagle-import") (part "R-US_R0201"))
    )
    (comp (ref "U$13")
      (value "TP_4MM_MED_PAD")
      (footprint "eagle-import:TP_4MM_MED_PAD")
      (libsource (lib "eagle-import") (part "TP_4MM_MED_PAD"))
    )
    (comp (ref "U$15")
      (value "4PAD")
      (footprint "eagle-import:4PAD")
      (libsource (lib "eagle-import") (part "4PAD"))
    )
    (comp (ref "U$16")
      (value "4PAD")
      (footprint "eagle-import:4PAD")
      (libsource (lib "eagle-import") (part "4PAD"))
    )
    (comp (ref "U4")
      (value "WS2818")
      (footprint "eagle-import:SO08")
      (libsource (lib "eagle-import") (part "WS2818"))
    )
    (comp (ref "C16")
      (value "C-EUC0201")
      (footprint "eagle-import:C0201")
      (libsource (lib "eagle-import") (part "C-EUC0201"))
    )
    (comp (ref "R46")
      (value "R-US_R0201")
      (footprint "eagle-import:R0201")
      (libsource (lib "eagle-import") (part "R-US_R0201"))
    )
    (comp (ref "R47")
      (value "R-US_R0201")
      (footprint "eagle-import:R0201")
      (libsource (lib "eagle-import") (part "R-US_R0201"))
    )
    (comp (ref "R48")
      (value "100")
      (footprint "eagle-import:R0201")
      (libsource (lib "eagle-import") (part "R-US_R0201"))
    )
    (comp (ref "U$61")
      (value "TP_4MM_MED_PAD")
      (footprint "eagle-import:TP_4MM_MED_PAD")
      (libsource (lib "eagle-import") (part "TP_4MM_MED_PAD"))
    )
    (comp (ref "U$63")
      (value "4PAD")
      (footprint "eagle-import:4PAD")
      (libsource (lib "eagle-import") (part "4PAD"))
    )
    (comp (ref "U$64")
      (value "4PAD")
      (footprint "eagle-import:4PAD")
      (libsource (lib "eagle-import") (part "4PAD"))
    )
    (comp (ref "U16")
      (value "WS2818")
      (footprint "eagle-import:SO08")
      (libsource (lib "eagle-import") (part "WS2818"))
    )
    (comp (ref "C18")
      (value "C-EUC0201")
      (footprint "eagle-import:C0201")
      (libsource (lib "eagle-import") (part "C-EUC0201"))
    )
    (comp (ref "R52")
      (value "R-US_R0201")
      (footprint "eagle-import:R0201")
      (libsource (lib "eagle-import") (part "R-US_R0201"))
    )
    (comp (ref "R53")
      (value "R-US_R0201")
      (footprint "eagle-import:R0201")
      (libsource (lib "eagle-import") (part "R-US_R0201"))
    )
    (comp (ref "R54")
      (value "100")
      (footprint "eagle-import:R0201")
      (libsource (lib "eagle-import") (part "R-US_R0201"))
    )
    (comp (ref "U$69")
      (value "TP_4MM_MED_PAD")
      (footprint "eagle-import:TP_4MM_MED_PAD")
      (libsource (lib "eagle-import") (part "TP_4MM_MED_PAD"))
    )
    (comp (ref "U$71")
      (value "4PAD")
      (footprint "eagle-import:4PAD")
      (libsource (lib "eagle-import") (part "4PAD"))
    )
    (comp (ref "U$72")
      (value "4PAD")
      (footprint "eagle-import:4PAD")
      (libsource (lib "eagle-import") (part "4PAD"))
    )
    (comp (ref "U18")
      (value "WS2818")
      (footprint "eagle-import:SO08")
      (libsource (lib "eagle-import") (part "WS2818"))
    )
    (comp (ref "C28")
      (value "C-EUC0201")
      (footprint "eagle-import:C0201")
      (libsource (lib "eagle-import") (part "C-EUC0201"))
    )
    (comp (ref "R82")
      (value "R-US_R0201")
      (footprint "eagle-import:R0201")
      (libsource (lib "eagle-import") (part "R-US_R0201"))
    )
    (comp (ref "R83")
      (value "R-US_R0201")
      (footprint "eagle-import:R0201")
      (libsource (lib "eagle-import") (part "R-US_R0201"))
    )
    (comp (ref "R84")
      (value "100")
      (footprint "eagle-import:R0201")
      (libsource (lib "eagle-import") (part "R-US_R0201"))
    )
    (comp (ref "U$109")
      (value "TP_4MM_MED_PAD")
      (footprint "eagle-import:TP_4MM_MED_PAD")
      (libsource (lib "eagle-import") (part "TP_4MM_MED_PAD"))
    )
    (comp (ref "U$111")
      (value "4PAD")
      (footprint "eagle-import:4PAD")
      (libsource (lib "eagle-import") (part "4PAD"))
    )
    (comp (ref "U$112")
      (value "4PAD")
      (footprint "eagle-import:4PAD")
      (libsource (lib "eagle-import") (part "4PAD"))
    )
    (comp (ref "U28")
      (value "WS2818")
      (footprint "eagle-import:SO08")
      (libsource (lib "eagle-import") (part "WS2818"))
    )
    (comp (ref "C13")
      (value "C-EUC0201")
      (footprint "eagle-import:C0201")
      (libsource (lib "eagle-import") (part "C-EUC0201"))
    )
    (comp (ref "R37")
      (value "R-US_R0201")
      (footprint "eagle-import:R0201")
      (libsource (lib "eagle-import") (part "R-US_R0201"))
    )
    (comp (ref "R38")
      (value "R-US_R0201")
      (footprint "eagle-import:R0201")
      (libsource (lib "eagle-import") (part "R-US_R0201"))
    )
    (comp (ref "R39")
      (value "100")
      (footprint "eagle-import:R0201")
      (libsource (lib "eagle-import") (part "R-US_R0201"))
    )
    (comp (ref "U$49")
      (value "TP_4MM_MED_PAD")
      (footprint "eagle-import:TP_4MM_MED_PAD")
      (libsource (lib "eagle-import") (part "TP_4MM_MED_PAD"))
    )
    (comp (ref "U$51")
      (value "4PAD")
      (footprint "eagle-import:4PAD")
      (libsource (lib "eagle-import") (part "4PAD"))
    )
    (comp (ref "U$52")
      (value "4PAD")
      (footprint "eagle-import:4PAD")
      (libsource (lib "eagle-import") (part "4PAD"))
    )
    (comp (ref "U13")
      (value "WS2818")
      (footprint "eagle-import:SO08")
      (libsource (lib "eagle-import") (part "WS2818"))
    )
    (comp (ref "C6")
      (value "C-EUC0201")
      (footprint "eagle-import:C0201")
      (libsource (lib "eagle-import") (part "C-EUC0201"))
    )
    (comp (ref "R16")
      (value "R-US_R0201")
      (footprint "eagle-import:R0201")
      (libsource (lib "eagle-import") (part "R-US_R0201"))
    )
    (comp (ref "R17")
      (value "R-US_R0201")
      (footprint "eagle-import:R0201")
      (libsource (lib "eagle-import") (part "R-US_R0201"))
    )
    (comp (ref "R18")
      (value "100")
      (footprint "eagle-import:R0201")
      (libsource (lib "eagle-import") (part "R-US_R0201"))
    )
    (comp (ref "U$21")
      (value "TP_4MM_MED_PAD")
      (footprint "eagle-import:TP_4MM_MED_PAD")
      (libsource (lib "eagle-import") (part "TP_4MM_MED_PAD"))
    )
    (comp (ref "U$23")
      (value "4PAD")
      (footprint "eagle-import:4PAD")
      (libsource (lib "eagle-import") (part "4PAD"))
    )
    (comp (ref "U$24")
      (value "4PAD")
      (footprint "eagle-import:4PAD")
      (libsource (lib "eagle-import") (part "4PAD"))
    )
    (comp (ref "U6")
      (value "WS2818")
      (footprint "eagle-import:SO08")
      (libsource (lib "eagle-import") (part "WS2818"))
    )
    (comp (ref "C10")
      (value "C-EUC0201")
      (footprint "eagle-import:C0201")
      (libsource (lib "eagle-import") (part "C-EUC0201"))
    )
    (comp (ref "R28")
      (value "R-US_R0201")
      (footprint "eagle-import:R0201")
      (libsource (lib "eagle-import") (part "R-US_R0201"))
    )
    (comp (ref "R29")
      (value "R-US_R0201")
      (footprint "eagle-import:R0201")
      (libsource (lib "eagle-import") (part "R-US_R0201"))
    )
    (comp (ref "R30")
      (value "100")
      (footprint "eagle-import:R0201")
      (libsource (lib "eagle-import") (part "R-US_R0201"))
    )
    (comp (ref "U$37")
      (value "TP_4MM_MED_PAD")
      (footprint "eagle-import:TP_4MM_MED_PAD")
      (libsource (lib "eagle-import") (part "TP_4MM_MED_PAD"))
    )
    (comp (ref "U$39")
      (value "4PAD")
      (footprint "eagle-import:4PAD")
      (libsource (lib "eagle-import") (part "4PAD"))
    )
    (comp (ref "U$40")
      (value "4PAD")
      (footprint "eagle-import:4PAD")
      (libsource (lib "eagle-import") (part "4PAD"))
    )
    (comp (ref "U10")
      (value "WS2818")
      (footprint "eagle-import:SO08")
      (libsource (lib "eagle-import") (part "WS2818"))
    )
    (comp (ref "C12")
      (value "C-EUC0201")
      (footprint "eagle-import:C0201")
      (libsource (lib "eagle-import") (part "C-EUC0201"))
    )
    (comp (ref "R34")
      (value "R-US_R0201")
      (footprint "eagle-import:R0201")
      (libsource (lib "eagle-import") (part "R-US_R0201"))
    )
    (comp (ref "R35")
      (value "R-US_R0201")
      (footprint "eagle-import:R0201")
      (libsource (lib "eagle-import") (part "R-US_R0201"))
    )
    (comp (ref "R36")
      (value "100")
      (footprint "eagle-import:R0201")
      (libsource (lib "eagle-import") (part "R-US_R0201"))
    )
    (comp (ref "U$45")
      (value "TP_4MM_MED_PAD")
      (footprint "eagle-import:TP_4MM_MED_PAD")
      (libsource (lib "eagle-import") (part "TP_4MM_MED_PAD"))
    )
    (comp (ref "U$47")
      (value "4PAD")
      (footprint "eagle-import:4PAD")
      (libsource (lib "eagle-import") (part "4PAD"))
    )
    (comp (ref "U$48")
      (value "4PAD")
      (footprint "eagle-import:4PAD")
      (libsource (lib "eagle-import") (part "4PAD"))
    )
    (comp (ref "U12")
      (value "WS2818")
      (footprint "eagle-import:SO08")
      (libsource (lib "eagle-import") (part "WS2818"))
    )
    (comp (ref "C24")
      (value "C-EUC0201")
      (footprint "eagle-import:C0201")
      (libsource (lib "eagle-import") (part "C-EUC0201"))
    )
    (comp (ref "R70")
      (value "R-US_R0201")
      (footprint "eagle-import:R0201")
      (libsource (lib "eagle-import") (part "R-US_R0201"))
    )
    (comp (ref "R71")
      (value "R-US_R0201")
      (footprint "eagle-import:R0201")
      (libsource (lib "eagle-import") (part "R-US_R0201"))
    )
    (comp (ref "R72")
      (value "100")
      (footprint "eagle-import:R0201")
      (libsource (lib "eagle-import") (part "R-US_R0201"))
    )
    (comp (ref "U$93")
      (value "TP_4MM_MED_PAD")
      (footprint "eagle-import:TP_4MM_MED_PAD")
      (libsource (lib "eagle-import") (part "TP_4MM_MED_PAD"))
    )
    (comp (ref "U$95")
      (value "4PAD")
      (footprint "eagle-import:4PAD")
      (libsource (lib "eagle-import") (part "4PAD"))
    )
    (comp (ref "U$96")
      (value "4PAD")
      (footprint "eagle-import:4PAD")
      (libsource (lib "eagle-import") (part "4PAD"))
    )
    (comp (ref "U24")
      (value "WS2818")
      (footprint "eagle-import:SO08")
      (libsource (lib "eagle-import") (part "WS2818"))
    )
    (comp (ref "C32")
      (value "C-EUC0201")
      (footprint "eagle-import:C0201")
      (libsource (lib "eagle-import") (part "C-EUC0201"))
    )
    (comp (ref "R94")
      (value "R-US_R0201")
      (footprint "eagle-import:R0201")
      (libsource (lib "eagle-import") (part "R-US_R0201"))
    )
    (comp (ref "R95")
      (value "R-US_R0201")
      (footprint "eagle-import:R0201")
      (libsource (lib "eagle-import") (part "R-US_R0201"))
    )
    (comp (ref "R96")
      (value "100")
      (footprint "eagle-import:R0201")
      (libsource (lib "eagle-import") (part "R-US_R0201"))
    )
    (comp (ref "U$125")
      (value "TP_4MM_MED_PAD")
      (footprint "eagle-import:TP_4MM_MED_PAD")
      (libsource (lib "eagle-import") (part "TP_4MM_MED_PAD"))
    )
    (comp (ref "U$127")
      (value "4PAD")
      (footprint "eagle-import:4PAD")
      (libsource (lib "eagle-import") (part "4PAD"))
    )
    (comp (ref "U$128")
      (value "4PAD")
      (footprint "eagle-import:4PAD")
      (libsource (lib "eagle-import") (part "4PAD"))
    )
    (comp (ref "U32")
      (value "WS2818")
      (footprint "eagle-import:SO08")
      (libsource (lib "eagle-import") (part "WS2818"))
    )
  )
  (nets
    (net (code "1") (name "BIN0") (class "Default")
      (node (ref "U$3") (pin "P$2") (pinfunction "P$2_P$2") (pintype "bidirectional"))
      (node (ref "U1") (pin "7") (pinfunction "BIN_7") (pintype "bidirectional"))
    )
    (net (code "2") (name "DIN0") (class "Default")
      (node (ref "R4") (pin "2") (pinfunction "2_2") (pintype "passive"))
      (node (ref "U$3") (pin "P$1") (pinfunction "P$1_P$1") (pintype "bidirectional"))
      (node (ref "U$4") (pin "P$2") (pinfunction "P$2_P$2") (pintype "bidirectional"))
      (node (ref "U$7") (pin "P$2") (pinfunction "P$2_P$2") (pintype "bidirectional"))
      (node (ref "U2") (pin "7") (pinfunction "BIN_7") (pintype "bidirectional"))
    )
    (net (code "3") (name "DOUT0") (class "Default")
      (node (ref "R1") (pin "2") (pinfunction "2_2") (pintype "passive"))
      (node (ref "R5") (pin "1") (pinfunction "1_1") (pintype "passive"))
      (node (ref "U$11") (pin "P$2") (pinfunction "P$2_P$2") (pintype "bidirectional"))
      (node (ref "U$4") (pin "P$1") (pinfunction "P$1_P$1") (pintype "bidirectional"))
      (node (ref "U$7") (pin "P$1") (pinfunction "P$1_P$1") (pintype "bidirectional"))
      (node (ref "U$8") (pin "P$2") (pinfunction "P$2_P$2") (pintype "bidirectional"))
      (node (ref "U3") (pin "7") (pinfunction "BIN_7") (pintype "bidirectional"))
    )
    (net (code "4") (name "DOUT1") (class "Default")
      (node (ref "R2") (pin "1") (pinfunction "1_1") (pintype "passive"))
      (node (ref "R7") (pin "2") (pinfunction "2_2") (pintype "passive"))
      (node (ref "U$11") (pin "P$1") (pinfunction "P$1_P$1") (pintype "bidirectional"))
      (node (ref "U$12") (pin "P$2") (pinfunction "P$2_P$2") (pintype "bidirectional"))
      (node (ref "U$15") (pin "P$2") (pinfunction "P$2_P$2") (pintype "bidirectional"))
      (node (ref "U$8") (pin "P$1") (pinfunction "P$1_P$1") (pintype "bidirectional"))
      (node (ref "U4") (pin "7") (pinfunction "BIN_7") (pintype "bidirectional"))
    )
    (net (code "5") (name "DOUT2") (class "Default")
      (node (ref "R10") (pin "2") (pinfunction "2_2") (pintype "passive"))
      (node (ref "R8") (pin "1") (pinfunction "1_1") (pintype "passive"))
      (node (ref "U$12") (pin "P$1") (pinfunction "P$1_P$1") (pintype "bidirectional"))
      (node (ref "U$15") (pin "P$1") (pinfunction "P$1_P$1") (pintype "bidirectional"))
      (node (ref "U$16") (pin "P$2") (pinfunction "P$2_P$2") (pintype "bidirectional"))
      (node (ref "U$19") (pin "P$2") (pinfunction "P$2_P$2") (pintype "bidirectional"))
      (node (ref "U5") (pin "7") (pinfunction "BIN_7") (pintype "bidirectional"))
    )
    (net (code "6") (name "DOUT3") (class "Default")
      (node (ref "R11") (pin "1") (pinfunction "1_1") (pintype "passive"))
      (node (ref "R13") (pin "2") (pinfunction "2_2") (pintype "passive"))
      (node (ref "U$16") (pin "P$1") (pinfunction "P$1_P$1") (pintype "bidirectional"))
      (node (ref "U$19") (pin "P$1") (pinfunction "P$1_P$1") (pintype "bidirectional"))
      (node (ref "U$20") (pin "P$2") (pinfunction "P$2_P$2") (pintype "bidirectional"))
      (node (ref "U$23") (pin "P$2") (pinfunction "P$2_P$2") (pintype "bidirectional"))
      (node (ref "U6") (pin "7") (pinfunction "BIN_7") (pintype "bidirectional"))
    )
    (net (code "7") (name "DOUT4") (class "Default")
      (node (ref "R14") (pin "1") (pinfunction "1_1") (pintype "passive"))
      (node (ref "R16") (pin "2") (pinfunction "2_2") (pintype "passive"))
      (node (ref "U$20") (pin "P$1") (pinfunction "P$1_P$1") (pintype "bidirectional"))
      (node (ref "U$23") (pin "P$1") (pinfunction "P$1_P$1") (pintype "bidirectional"))
      (node (ref "U$24") (pin "P$2") (pinfunction "P$2_P$2") (pintype "bidirectional"))
      (node (ref "U$27") (pin "P$2") (pinfunction "P$2_P$2") (pintype "bidirectional"))
      (node (ref "U7") (pin "7") (pinfunction "BIN_7") (pintype "bidirectional"))
    )
    (net (code "8") (name "DOUT5") (class "Default")
      (node (ref "R17") (pin "1") (pinfunction "1_1") (pintype "passive"))
      (node (ref "R19") (pin "2") (pinfunction "2_2") (pintype "passive"))
      (node (ref "U$24") (pin "P$1") (pinfunction "P$1_P$1") (pintype "bidirectional"))
      (node (ref "U$27") (pin "P$1") (pinfunction "P$1_P$1") (pintype "bidirectional"))
      (node (ref "U$28") (pin "P$2") (pinfunction "P$2_P$2") (pintype "bidirectional"))
      (node (ref "U$31") (pin "P$2") (pinfunction "P$2_P$2") (pintype "bidirectional"))
      (node (ref "U8") (pin "7") (pinfunction "BIN_7") (pintype "bidirectional"))
    )
    (net (code "9") (name "DOUT6") (class "Default")
      (node (ref "R20") (pin "1") (pinfunction "1_1") (pintype "passive"))
      (node (ref "R22") (pin "2") (pinfunction "2_2") (pintype "passive"))
      (node (ref "U$28") (pin "P$1") (pinfunction "P$1_P$1") (pintype "bidirectional"))
      (node (ref "U$31") (pin "P$1") (pinfunction "P$1_P$1") (pintype "bidirectional"))
      (node (ref "U$32") (pin "P$2") (pinfunction "P$2_P$2") (pintype "bidirectional"))
      (node (ref "U$35") (pin "P$2") (pinfunction "P$2_P$2") (pintype "bidirectional"))
      (node (ref "U9") (pin "7") (pinfunction "BIN_7") (pintype "bidirectional"))
    )
    (net (code "10") (name "DOUT7") (class "Default")
      (node (ref "R23") (pin "1") (pinfunction "1_1") (pintype "passive"))
      (node (ref "R25") (pin "2") (pinfunction "2_2") (pintype "passive"))
      (node (ref "U$32") (pin "P$1") (pinfunction "P$1_P$1") (pintype "bidirectional"))
      (node (ref "U$35") (pin "P$1") (pinfunction "P$1_P$1") (pintype "bidirectional"))
      (node (ref "U$36") (pin "P$2") (pinfunction "P$2_P$2") (pintype "bidirectional"))
      (node (ref "U$39") (pin "P$2") (pinfunction "P$2_P$2") (pintype "bidirectional"))
      (node (ref "U10") (pin "7") (pinfunction "BIN_7") (pintype "bidirectional"))
    )
    (net (code "11") (name "DOUT8") (class "Default")
      (node (ref "R26") (pin "1") (pinfunction "1_1") (pintype "passive"))
      (node (ref "R28") (pin "2") (pinfunction "2_2") (pintype "passive"))
      (node (ref "U$36") (pin "P$1") (pinfunction "P$1_P$1") (pintype "bidirectional"))
      (node (ref "U$39") (pin "P$1") (pinfunction "P$1_P$1") (pintype "bidirectional"))
      (node (ref "U$40") (pin "P$2") (pinfunction "P$2_P$2") (pintype "bidirectional"))
      (node (ref "U$43") (pin "P$2") (pinfunction "P$2_P$2") (pintype "bidirectional"))
      (node (ref "U11") (pin "7") (pinfunction "BIN_7") (pintype "bidirectional"))
    )
    (net (code "12") (name "DOUT9") (class "Default")
      (node (ref "R29") (pin "1") (pinfunction "1_1") (pintype "passive"))
      (node (ref "R31") (pin "2") (pinfunction "2_2") (pintype "passive"))
      (node (ref "U$40") (pin "P$1") (pinfunction "P$1_P$1") (pintype "bidirectional"))
      (node (ref "U$43") (pin "P$1") (pinfunction "P$1_P$1") (pintype "bidirectional"))
      (node (ref "U$44") (pin "P$2") (pinfunction "P$2_P$2") (pintype "bidirectional"))
      (node (ref "U$47") (pin "P$2") (pinfunction "P$2_P$2") (pintype "bidirectional"))
      (node (ref "U12") (pin "7") (pinfunction "BIN_7") (pintype "bidirectional"))
    )
    (net (code "13") (name "DOUT10") (class "Default")
      (node (ref "R32") (pin "1") (pinfunction "1_1") (pintype "passive"))
      (node (ref "R34") (pin "2") (pinfunction "2_2") (pintype "passive"))
      (node (ref "U$44") (pin "P$1") (pinfunction "P$1_P$1") (pintype "bidirectional"))
      (node (ref "U$47") (pin "P$1") (pinfunction "P$1_P$1") (pintype "bidirectional"))
      (node (ref "U$48") (pin "P$2") (pinfunction "P$2_P$2") (pintype "bidirectional"))
      (node (ref "U$51") (pin "P$2") (pinfunction "P$2_P$2") (pintype "bidirectional"))
      (node (ref "U13") (pin "7") (pinfunction "BIN_7") (pintype "bidirectional"))
    )
    (net (code "14") (name "DOUT11") (class "Default")
      (node (ref "R35") (pin "1") (pinfunction "1_1") (pintype "passive"))
      (node (ref "R37") (pin "2") (pinfunction "2_2") (pintype "passive"))
      (node (ref "U$48") (pin "P$1") (pinfunction "P$1_P$1") (pintype "bidirectional"))
      (node (ref "U$51") (pin "P$1") (pinfunction "P$1_P$1") (pintype "bidirectional"))
      (node (ref "U$52") (pin "P$2") (pinfunction "P$2_P$2") (pintype "bidirectional"))
      (node (ref "U$55") (pin "P$2") (pinfunction "P$2_P$2") (pintype "bidirectional"))
      (node (ref "U14") (pin "7") (pinfunction "BIN_7") (pintype "bidirectional"))
    )
    (net (code "15") (name "DOUT12") (class "Default")
      (node (ref "R38") (pin "1") (pinfunction "1_1") (pintype "passive"))
      (node (ref "R40") (pin "2") (pinfunction "2_2") (pintype "passive"))
      (node (ref "U$52") (pin "P$1") (pinfunction "P$1_P$1") (pintype "bidirectional"))
      (node (ref "U$55") (pin "P$1") (pinfunction "P$1_P$1") (pintype "bidirectional"))
      (node (ref "U$56") (pin "P$2") (pinfunction "P$2_P$2") (pintype "bidirectional"))
      (node (ref "U$59") (pin "P$2") (pinfunction "P$2_P$2") (pintype "bidirectional"))
      (node (ref "U15") (pin "7") (pinfunction "BIN_7") (pintype "bidirectional"))
    )
    (net (code "16") (name "DOUT13") (class "Default")
      (node (ref "R41") (pin "1") (pinfunction "1_1") (pintype "passive"))
      (node (ref "R43") (pin "2") (pinfunction "2_2") (pintype "passive"))
      (node (ref "U$56") (pin "P$1") (pinfunction "P$1_P$1") (pintype "bidirectional"))
      (node (ref "U$59") (pin "P$1") (pinfunction "P$1_P$1") (pintype "bidirectional"))
      (node (ref "U$60") (pin "P$2") (pinfunction "P$2_P$2") (pintype "bidirectional"))
      (node (ref "U$63") (pin "P$2") (pinfunction "P$2_P$2") (pintype "bidirectional"))
      (node (ref "U16") (pin "7") (pinfunction "BIN_7") (pintype "bidirectional"))
    )
    (net (code "17") (name "DOUT14") (class "Default")
      (node (ref "R44") (pin "1") (pinfunction "1_1") (pintype "passive"))
      (node (ref "R46") (pin "2") (pinfunction "2_2") (pintype "passive"))
      (node (ref "U$60") (pin "P$1") (pinfunction "P$1_P$1") (pintype "bidirectional"))
      (node (ref "U$63") (pin "P$1") (pinfunction "P$1_P$1") (pintype "bidirectional"))
      (node (ref "U$64") (pin "P$2") (pinfunction "P$2_P$2") (pintype "bidirectional"))
      (node (ref "U$67") (pin "P$2") (pinfunction "P$2_P$2") (pintype "bidirectional"))
      (node (ref "U17") (pin "7") (pinfunction "BIN_7") (pintype "bidirectional"))
    )
    (net (code "18") (name "DOUT15") (class "Default")
      (node (ref "R47") (pin "1") (pinfunction "1_1") (pintype "passive"))
      (node (ref "R49") (pin "2") (pinfunction "2_2") (pintype "passive"))
      (node (ref "U$64") (pin "P$1") (pinfunction "P$1_P$1") (pintype "bidirectional"))
      (node (ref "U$67") (pin "P$1") (pinfunction "P$1_P$1") (pintype "bidirectional"))
      (node (ref "U$68") (pin "P$2") (pinfunction "P$2_P$2") (pintype "bidirectional"))
      (node (ref "U$71") (pin "P$2") (pinfunction "P$2_P$2") (pintype "bidirectional"))
      (node (ref "U18") (pin "7") (pinfunction "BIN_7") (pintype "bidirectional"))
    )
    (net (code "19") (name "DOUT16") (class "Default")
      (node (ref "R50") (pin "1") (pinfunction "1_1") (pintype "passive"))
      (node (ref "R52") (pin "2") (pinfunction "2_2") (pintype "passive"))
      (node (ref "U$68") (pin "P$1") (pinfunction "P$1_P$1") (pintype "bidirectional"))
      (node (ref "U$71") (pin "P$1") (pinfunction "P$1_P$1") (pintype "bidirectional"))
      (node (ref "U$72") (pin "P$2") (pinfunction "P$2_P$2") (pintype "bidirectional"))
      (node (ref "U$75") (pin "P$2") (pinfunction "P$2_P$2") (pintype "bidirectional"))
      (node (ref "U19") (pin "7") (pinfunction "BIN_7") (pintype "bidirectional"))
    )
    (net (code "20") (name "DOUT17") (class "Default")
      (node (ref "R53") (pin "1") (pinfunction "1_1") (pintype "passive"))
      (node (ref "R55") (pin "2") (pinfunction "2_2") (pintype "passive"))
      (node (ref "U$72") (pin "P$1") (pinfunction "P$1_P$1") (pintype "bidirectional"))
      (node (ref "U$75") (pin "P$1") (pinfunction "P$1_P$1") (pintype "bidirectional"))
      (node (ref "U$76") (pin "P$2") (pinfunction "P$2_P$2") (pintype "bidirectional"))
      (node (ref "U$79") (pin "P$2") (pinfunction "P$2_P$2") (pintype "bidirectional"))
      (node (ref "U20") (pin "7") (pinfunction "BIN_7") (pintype "bidirectional"))
    )
    (net (code "21") (name "DOUT18") (class "Default")
      (node (ref "R56") (pin "1") (pinfunction "1_1") (pintype "passive"))
      (node (ref "R58") (pin "2") (pinfunction "2_2") (pintype "passive"))
      (node (ref "U$76") (pin "P$1") (pinfunction "P$1_P$1") (pintype "bidirectional"))
      (node (ref "U$79") (pin "P$1") (pinfunction "P$1_P$1") (pintype "bidirectional"))
      (node (ref "U$80") (pin "P$2") (pinfunction "P$2_P$2") (pintype "bidirectional"))
      (node (ref "U$83") (pin "P$2") (pinfunction "P$2_P$2") (pintype "bidirectional"))
      (node (ref "U21") (pin "7") (pinfunction "BIN_7") (pintype "bidirectional"))
    )
    (net (code "22") (name "DOUT19") (class "Default")
      (node (ref "R59") (pin "1") (pinfunction "1_1") (pintype "passive"))
      (node (ref "R61") (pin "2") (pinfunction "2_2") (pintype "passive"))
      (node (ref "U$80") (pin "P$1") (pinfunction "P$1_P$1") (pintype "bidirectional"))
      (node (ref "U$83") (pin "P$1") (pinfunction "P$1_P$1") (pintype "bidirectional"))
      (node (ref "U$84") (pin "P$2") (pinfunction "P$2_P$2") (pintype "bidirectional"))
      (node (ref "U$87") (pin "P$2") (pinfunction "P$2_P$2") (pintype "bidirectional"))
      (node (ref "U22") (pin "7") (pinfunction "BIN_7") (pintype "bidirectional"))
    )
    (net (code "23") (name "DOUT20") (class "Default")
      (node (ref "R62") (pin "1") (pinfunction "1_1") (pintype "passive"))
      (node (ref "R64") (pin "2") (pinfunction "2_2") (pintype "passive"))
      (node (ref "U$84") (pin "P$1") (pinfunction "P$1_P$1") (pintype "bidirectional"))
      (node (ref "U$87") (pin "P$1") (pinfunction "P$1_P$1") (pintype "bidirectional"))
      (node (ref "U$88") (pin "P$2") (pinfunction "P$2_P$2") (pintype "bidirectional"))
      (node (ref "U$91") (pin "P$2") (pinfunction "P$2_P$2") (pintype "bidirectional"))
      (node (ref "U23") (pin "7") (pinfunction "BIN_7") (pintype "bidirectional"))
    )
    (net (code "24") (name "DOUT21") (class "Default")
      (node (ref "R65") (pin "1") (pinfunction "1_1") (pintype "passive"))
      (node (ref "R67") (pin "2") (pinfunction "2_2") (pintype "passive"))
      (node (ref "U$88") (pin "P$1") (pinfunction "P$1_P$1") (pintype "bidirectional"))
      (node (ref "U$91") (pin "P$1") (pinfunction "P$1_P$1") (pintype "bidirectional"))
      (node (ref "U$92") (pin "P$2") (pinfunction "P$2_P$2") (pintype "bidirectional"))
      (node (ref "U$95") (pin "P$2") (pinfunction "P$2_P$2") (pintype "bidirectional"))
      (node (ref "U24") (pin "7") (pinfunction "BIN_7") (pintype "bidirectional"))
    )
    (net (code "25") (name "DOUT22") (class "Default")
      (node (ref "R68") (pin "1") (pinfunction "1_1") (pintype "passive"))
      (node (ref "R70") (pin "2") (pinfunction "2_2") (pintype "passive"))
      (node (ref "U$92") (pin "P$1") (pinfunction "P$1_P$1") (pintype "bidirectional"))
      (node (ref "U$95") (pin "P$1") (pinfunction "P$1_P$1") (pintype "bidirectional"))
      (node (ref "U$96") (pin "P$2") (pinfunction "P$2_P$2") (pintype "bidirectional"))
      (node (ref "U$99") (pin "P$2") (pinfunction "P$2_P$2") (pintype "bidirectional"))
      (node (ref "U25") (pin "7") (pinfunction "BIN_7") (pintype "bidirectional"))
    )
    (net (code "26") (name "DOUT23") (class "Default")
      (node (ref "R71") (pin "1") (pinfunction "1_1") (pintype "passive"))
      (node (ref "R73") (pin "2") (pinfunction "2_2") (pintype "passive"))
      (node (ref "U$100") (pin "P$2") (pinfunction "P$2_P$2") (pintype "bidirectional"))
      (node (ref "U$103") (pin "P$2") (pinfunction "P$2_P$2") (pintype "bidirectional"))
      (node (ref "U$96") (pin "P$1") (pinfunction "P$1_P$1") (pintype "bidirectional"))
      (node (ref "U$99") (pin "P$1") (pinfunction "P$1_P$1") (pintype "bidirectional"))
      (node (ref "U26") (pin "7") (pinfunction "BIN_7") (pintype "bidirectional"))
    )
    (net (code "27") (name "DOUT24") (class "Default")
      (node (ref "R74") (pin "1") (pinfunction "1_1") (pintype "passive"))
      (node (ref "R76") (pin "2") (pinfunction "2_2") (pintype "passive"))
      (node (ref "U$100") (pin "P$1") (pinfunction "P$1_P$1") (pintype "bidirectional"))
      (node (ref "U$103") (pin "P$1") (pinfunction "P$1_P$1") (pintype "bidirectional"))
      (node (ref "U$104") (pin "P$2") (pinfunction "P$2_P$2") (pintype "bidirectional"))
      (node (ref "U$107") (pin "P$2") (pinfunction "P$2_P$2") (pintype "bidirectional"))
      (node (ref "U27") (pin "7") (pinfunction "BIN_7") (pintype "bidirectional"))
    )
    (net (code "28") (name "DOUT25") (class "Default")
      (node (ref "R77") (pin "1") (pinfunction "1_1") (pintype "passive"))
      (node (ref "R79") (pin "2") (pinfunction "2_2") (pintype "passive"))
      (node (ref "U$104") (pin "P$1") (pinfunction "P$1_P$1") (pintype "bidirectional"))
      (node (ref "U$107") (pin "P$1") (pinfunction "P$1_P$1") (pintype "bidirectional"))
      (node (ref "U$108") (pin "P$2") (pinfunction "P$2_P$2") (pintype "bidirectional"))
      (node (ref "U$111") (pin "P$2") (pinfunction "P$2_P$2") (pintype "bidirectional"))
      (node (ref "U28") (pin "7") (pinfunction "BIN_7") (pintype "bidirectional"))
    )
    (net (code "29") (name "DOUT26") (class "Default")
      (node (ref "R80") (pin "1") (pinfunction "1_1") (pintype "passive"))
      (node (ref "R82") (pin "2") (pinfunction "2_2") (pintype "passive"))
      (node (ref "U$108") (pin "P$1") (pinfunction "P$1_P$1") (pintype "bidirectional"))
      (node (ref "U$111") (pin "P$1") (pinfunction "P$1_P$1") (pintype "bidirectional"))
      (node (ref "U$112") (pin "P$2") (pinfunction "P$2_P$2") (pintype "bidirectional"))
      (node (ref "U$115") (pin "P$2") (pinfunction "P$2_P$2") (pintype "bidirectional"))
      (node (ref "U29") (pin "7") (pinfunction "BIN_7") (pintype "bidirectional"))
    )
    (net (code "30") (name "DOUT27") (class "Default")
      (node (ref "R83") (pin "1") (pinfunction "1_1") (pintype "passive"))
      (node (ref "R85") (pin "2") (pinfunction "2_2") (pintype "passive"))
      (node (ref "U$112") (pin "P$1") (pinfunction "P$1_P$1") (pintype "bidirectional"))
      (node (ref "U$115") (pin "P$1") (pinfunction "P$1_P$1") (pintype "bidirectional"))
      (node (ref "U$116") (pin "P$2") (pinfunction "P$2_P$2") (pintype "bidirectional"))
      (node (ref "U$119") (pin "P$2") (pinfunction "P$2_P$2") (pintype "bidirectional"))
      (node (ref "U30") (pin "7") (pinfunction "BIN_7") (pintype "bidirectional"))
    )
    (net (code "31") (name "DOUT28") (class "Default")
      (node (ref "R86") (pin "1") (pinfunction "1_1") (pintype "passive"))
      (node (ref "R88") (pin "2") (pinfunction "2_2") (pintype "passive"))
      (node (ref "U$116") (pin "P$1") (pinfunction "P$1_P$1") (pintype "bidirectional"))
      (node (ref "U$119") (pin "P$1") (pinfunction "P$1_P$1") (pintype "bidirectional"))
      (node (ref "U$120") (pin "P$2") (pinfunction "P$2_P$2") (pintype "bidirectional"))
      (node (ref "U$123") (pin "P$2") (pinfunction "P$2_P$2") (pintype "bidirectional"))
      (node (ref "U31") (pin "7") (pinfunction "BIN_7") (pintype "bidirectional"))
    )
    (net (code "32") (name "DOUT29") (class "Default")
      (node (ref "R89") (pin "1") (pinfunction "1_1") (pintype "passive"))
      (node (ref "R91") (pin "2") (pinfunction "2_2") (pintype "passive"))
      (node (ref "U$120") (pin "P$1") (pinfunction "P$1_P$1") (pintype "bidirectional"))
      (node (ref "U$123") (pin "P$1") (pinfunction "P$1_P$1") (pintype "bidirectional"))
      (node (ref "U$124") (pin "P$2") (pinfunction "P$2_P$2") (pintype "bidirectional"))
      (node (ref "U$127") (pin "P$2") (pinfunction "P$2_P$2") (pintype "bidirectional"))
      (node (ref "U32") (pin "7") (pinfunction "BIN_7") (pintype "bidirectional"))
    )
    (net (code "33") (name "DOUT30") (class "Default")
      (node (ref "R92") (pin "1") (pinfunction "1_1") (pintype "passive"))
      (node (ref "R94") (pin "2") (pinfunction "2_2") (pintype "passive"))
      (node (ref "U$124") (pin "P$1") (pinfunction "P$1_P$1") (pintype "bidirectional"))
      (node (ref "U$127") (pin "P$1") (pinfunction "P$1_P$1") (pintype "bidirectional"))
      (node (ref "U$128") (pin "P$2") (pinfunction "P$2_P$2") (pintype "bidirectional"))
    )
    (net (code "34") (name "DOUT31") (class "Default")
      (node (ref "R95") (pin "1") (pinfunction "1_1") (pintype "passive"))
      (node (ref "U$128") (pin "P$1") (pinfunction "P$1_P$1") (pintype "bidirectional"))
    )
    (net (code "35") (name "GND") (class "Default")
      (node (ref "C1") (pin "2") (pinfunction "2_2") (pintype "passive"))
      (node (ref "C10") (pin "2") (pinfunction "2_2") (pintype "passive"))
      (node (ref "C11") (pin "2") (pinfunction "2_2") (pintype "passive"))
      (node (ref "C12") (pin "2") (pinfunction "2_2") (pintype "passive"))
      (node (ref "C13") (pin "2") (pinfunction "2_2") (pintype "passive"))
      (node (ref "C14") (pin "2") (pinfunction "2_2") (pintype "passive"))
      (node (ref "C15") (pin "2") (pinfunction "2_2") (pintype "passive"))
      (node (ref "C16") (pin "2") (pinfunction "2_2") (pintype "passive"))
      (node (ref "C17") (pin "2") (pinfunction "2_2") (pintype "passive"))
      (node (ref "C18") (pin "2") (pinfunction "2_2") (pintype "passive"))
      (node (ref "C19") (pin "2") (pinfunction "2_2") (pintype "passive"))
      (node (ref "C2") (pin "2") (pinfunction "2_2") (pintype "passive"))
      (node (ref "C20") (pin "2") (pinfunction "2_2") (pintype "passive"))
      (node (ref "C21") (pin "2") (pinfunction "2_2") (pintype "passive"))
      (node (ref "C22") (pin "2") (pinfunction "2_2") (pintype "passive"))
      (node (ref "C23") (pin "2") (pinfunction "2_2") (pintype "passive"))
      (node (ref "C24") (pin "2") (pinfunction "2_2") (pintype "passive"))
      (node (ref "C25") (pin "2") (pinfunction "2_2") (pintype "passive"))
      (node (ref "C26") (pin "2") (pinfunction "2_2") (pintype "passive"))
      (node (ref "C27") (pin "2") (pinfunction "2_2") (pintype "passive"))
      (node (ref "C28") (pin "2") (pinfunction "2_2") (pintype "passive"))
      (node (ref "C29") (pin "2") (pinfunction "2_2") (pintype "passive"))
      (node (ref "C3") (pin "2") (pinfunction "2_2") (pintype "passive"))
      (node (ref "C30") (pin "2") (pinfunction "2_2") (pintype "passive"))
      (node (ref "C31") (pin "2") (pinfunction "2_2") (pintype "passive"))
      (node (ref "C32") (pin "2") (pinfunction "2_2") (pintype "passive"))
      (node (ref "C4") (pin "2") (pinfunction "2_2") (pintype "passive"))
      (node (ref "C5") (pin "2") (pinfunction "2_2") (pintype "passive"))
      (node (ref "C6") (pin "2") (pinfunction "2_2") (pintype "passive"))
      (node (ref "C7") (pin "2") (pinfunction "2_2") (pintype "passive"))
      (node (ref "C8") (pin "2") (pinfunction "2_2") (pintype "passive"))
      (node (ref "C9") (pin "2") (pinfunction "2_2") (pintype "passive"))
      (node (ref "U$100") (pin "P$3") (pinfunction "P$3_P$3") (pintype "bidirectional"))
      (node (ref "U$103") (pin "P$3") (pinfunction "P$3_P$3") (pintype "bidirectional"))
      (node (ref "U$104") (pin "P$3") (pinfunction "P$3_P$3") (pintype "bidirectional"))
      (node (ref "U$107") (pin "P$3") (pinfunction "P$3_P$3") (pintype "bidirectional"))
      (node (ref "U$108") (pin "P$3") (pinfunction "P$3_P$3") (pintype "bidirectional"))
      (node (ref "U$11") (pin "P$3") (pinfunction "P$3_P$3") (pintype "bidirectional"))
      (node (ref "U$111") (pin "P$3") (pinfunction "P$3_P$3") (pintype "bidirectional"))
      (node (ref "U$112") (pin "P$3") (pinfunction "P$3_P$3") (pintype "bidirectional"))
      (node (ref "U$115") (pin "P$3") (pinfunction "P$3_P$3") (pintype "bidirectional"))
      (node (ref "U$116") (pin "P$3") (pinfunction "P$3_P$3") (pintype "bidirectional"))
      (node (ref "U$119") (pin "P$3") (pinfunction "P$3_P$3") (pintype "bidirectional"))
      (node (ref "U$12") (pin "P$3") (pinfunction "P$3_P$3") (pintype "bidirectional"))
      (node (ref "U$120") (pin "P$3") (pinfunction "P$3_P$3") (pintype "bidirectional"))
      (node (ref "U$123") (pin "P$3") (pinfunction "P$3_P$3") (pintype "bidirectional"))
      (node (ref "U$124") (pin "P$3") (pinfunction "P$3_P$3") (pintype "bidirectional"))
      (node (ref "U$127") (pin "P$3") (pinfunction "P$3_P$3") (pintype "bidirectional"))
      (node (ref "U$128") (pin "P$3") (pinfunction "P$3_P$3") (pintype "bidirectional"))
      (node (ref "U$15") (pin "P$3") (pinfunction "P$3_P$3") (pintype "bidirectional"))
      (node (ref "U$16") (pin "P$3") (pinfunction "P$3_P$3") (pintype "bidirectional"))
      (node (ref "U$19") (pin "P$3") (pinfunction "P$3_P$3") (pintype "bidirectional"))
      (node (ref "U$20") (pin "P$3") (pinfunction "P$3_P$3") (pintype "bidirectional"))
      (node (ref "U$23") (pin "P$3") (pinfunction "P$3_P$3") (pintype "bidirectional"))
      (node (ref "U$24") (pin "P$3") (pinfunction "P$3_P$3") (pintype "bidirectional"))
      (node (ref "U$27") (pin "P$3") (pinfunction "P$3_P$3") (pintype "bidirectional"))
      (node (ref "U$28") (pin "P$3") (pinfunction "P$3_P$3") (pintype "bidirectional"))
      (node (ref "U$3") (pin "P$3") (pinfunction "P$3_P$3") (pintype "bidirectional"))
      (node (ref "U$31") (pin "P$3") (pinfunction "P$3_P$3") (pintype "bidirectional"))
      (node (ref "U$32") (pin "P$3") (pinfunction "P$3_P$3") (pintype "bidirectional"))
      (node (ref "U$35") (pin "P$3") (pinfunction "P$3_P$3") (pintype "bidirectional"))
      (node (ref "U$36") (pin "P$3") (pinfunction "P$3_P$3") (pintype "bidirectional"))
      (node (ref "U$39") (pin "P$3") (pinfunction "P$3_P$3") (pintype "bidirectional"))
      (node (ref "U$4") (pin "P$3") (pinfunction "P$3_P$3") (pintype "bidirectional"))
      (node (ref "U$40") (pin "P$3") (pinfunction "P$3_P$3") (pintype "bidirectional"))
      (node (ref "U$43") (pin "P$3") (pinfunction "P$3_P$3") (pintype "bidirectional"))
      (node (ref "U$44") (pin "P$3") (pinfunction "P$3_P$3") (pintype "bidirectional"))
      (node (ref "U$47") (pin "P$3") (pinfunction "P$3_P$3") (pintype "bidirectional"))
      (node (ref "U$48") (pin "P$3") (pinfunction "P$3_P$3") (pintype "bidirectional"))
      (node (ref "U$51") (pin "P$3") (pinfunction "P$3_P$3") (pintype "bidirectional"))
      (node (ref "U$52") (pin "P$3") (pinfunction "P$3_P$3") (pintype "bidirectional"))
      (node (ref "U$55") (pin "P$3") (pinfunction "P$3_P$3") (pintype "bidirectional"))
      (node (ref "U$56") (pin "P$3") (pinfunction "P$3_P$3") (pintype "bidirectional"))
      (node (ref "U$59") (pin "P$3") (pinfunction "P$3_P$3") (pintype "bidirectional"))
      (node (ref "U$60") (pin "P$3") (pinfunction "P$3_P$3") (pintype "bidirectional"))
      (node (ref "U$63") (pin "P$3") (pinfunction "P$3_P$3") (pintype "bidirectional"))
      (node (ref "U$64") (pin "P$3") (pinfunction "P$3_P$3") (pintype "bidirectional"))
      (node (ref "U$67") (pin "P$3") (pinfunction "P$3_P$3") (pintype "bidirectional"))
      (node (ref "U$68") (pin "P$3") (pinfunction "P$3_P$3") (pintype "bidirectional"))
      (node (ref "U$7") (pin "P$3") (pinfunction "P$3_P$3") (pintype "bidirectional"))
      (node (ref "U$71") (pin "P$3") (pinfunction "P$3_P$3") (pintype "bidirectional"))
      (node (ref "U$72") (pin "P$3") (pinfunction "P$3_P$3") (pintype "bidirectional"))
      (node (ref "U$75") (pin "P$3") (pinfunction "P$3_P$3") (pintype "bidirectional"))
      (node (ref "U$76") (pin "P$3") (pinfunction "P$3_P$3") (pintype "bidirectional"))
      (node (ref "U$79") (pin "P$3") (pinfunction "P$3_P$3") (pintype "bidirectional"))
      (node (ref "U$8") (pin "P$3") (pinfunction "P$3_P$3") (pintype "bidirectional"))
      (node (ref "U$80") (pin "P$3") (pinfunction "P$3_P$3") (pintype "bidirectional"))
      (node (ref "U$83") (pin "P$3") (pinfunction "P$3_P$3") (pintype "bidirectional"))
      (node (ref "U$84") (pin "P$3") (pinfunction "P$3_P$3") (pintype "bidirectional"))
      (node (ref "U$87") (pin "P$3") (pinfunction "P$3_P$3") (pintype "bidirectional"))
      (node (ref "U$88") (pin "P$3") (pinfunction "P$3_P$3") (pintype "bidirectional"))
      (node (ref "U$91") (pin "P$3") (pinfunction "P$3_P$3") (pintype "bidirectional"))
      (node (ref "U$92") (pin "P$3") (pinfunction "P$3_P$3") (pintype "bidirectional"))
      (node (ref "U$95") (pin "P$3") (pinfunction "P$3_P$3") (pintype "bidirectional"))
      (node (ref "U$96") (pin "P$3") (pinfunction "P$3_P$3") (pintype "bidirectional"))
      (node (ref "U$99") (pin "P$3") (pinfunction "P$3_P$3") (pintype "bidirectional"))
      (node (ref "U1") (pin "6") (pinfunction "GND_6") (pintype "bidirectional"))
      (node (ref "U10") (pin "6") (pinfunction "GND_6") (pintype "bidirectional"))
      (node (ref "U11") (pin "6") (pinfunction "GND_6") (pintype "bidirectional"))
      (node (ref "U12") (pin "6") (pinfunction "GND_6") (pintype "bidirectional"))
      (node (ref "U13") (pin "6") (pinfunction "GND_6") (pintype "bidirectional"))
      (node (ref "U14") (pin "6") (pinfunction "GND_6") (pintype "bidirectional"))
      (node (ref "U15") (pin "6") (pinfunction "GND_6") (pintype "bidirectional"))
      (node (ref "U16") (pin "6") (pinfunction "GND_6") (pintype "bidirectional"))
      (node (ref "U17") (pin "6") (pinfunction "GND_6") (pintype "bidirectional"))
      (node (ref "U18") (pin "6") (pinfunction "GND_6") (pintype "bidirectional"))
      (node (ref "U19") (pin "6") (pinfunction "GND_6") (pintype "bidirectional"))
      (node (ref "U2") (pin "6") (pinfunction "GND_6") (pintype "bidirectional"))
      (node (ref "U20") (pin "6") (pinfunction "GND_6") (pintype "bidirectional"))
      (node (ref "U21") (pin "6") (pinfunction "GND_6") (pintype "bidirectional"))
      (node (ref "U22") (pin "6") (pinfunction "GND_6") (pintype "bidirectional"))
      (node (ref "U23") (pin "6") (pinfunction "GND_6") (pintype "bidirectional"))
      (node (ref "U24") (pin "6") (pinfunction "GND_6") (pintype "bidirectional"))
      (node (ref "U25") (pin "6") (pinfunction "GND_6") (pintype "bidirectional"))
      (node (ref "U26") (pin "6") (pinfunction "GND_6") (pintype "bidirectional"))
      (node (ref "U27") (pin "6") (pinfunction "GND_6") (pintype "bidirectional"))
      (node (ref "U28") (pin "6") (pinfunction "GND_6") (pintype "bidirectional"))
      (node (ref "U29") (pin "6") (pinfunction "GND_6") (pintype "bidirectional"))
      (node (ref "U3") (pin "6") (pinfunction "GND_6") (pintype "bidirectional"))
      (node (ref "U30") (pin "6") (pinfunction "GND_6") (pintype "bidirectional"))
      (node (ref "U31") (pin "6") (pinfunction "GND_6") (pintype "bidirectional"))
      (node (ref "U32") (pin "6") (pinfunction "GND_6") (pintype "bidirectional"))
      (node (ref "U4") (pin "6") (pinfunction "GND_6") (pintype "bidirectional"))
      (node (ref "U5") (pin "6") (pinfunction "GND_6") (pintype "bidirectional"))
      (node (ref "U6") (pin "6") (pinfunction "GND_6") (pintype "bidirectional"))
      (node (ref "U7") (pin "6") (pinfunction "GND_6") (pintype "bidirectional"))
      (node (ref "U8") (pin "6") (pinfunction "GND_6") (pintype "bidirectional"))
      (node (ref "U9") (pin "6") (pinfunction "GND_6") (pintype "bidirectional"))
    )
    (net (code "36") (name "NEG_PAD0") (class "Default")
      (node (ref "U$1") (pin "P$1") (pinfunction "0_P$1") (pintype "bidirectional"))
      (node (ref "U1") (pin "1") (pinfunction "OUTR_1") (pintype "bidirectional"))
      (node (ref "U1") (pin "2") (pinfunction "OUTG_2") (pintype "bidirectional"))
      (node (ref "U1") (pin "3") (pinfunction "OUTB_3") (pintype "bidirectional"))
    )
    (net (code "37") (name "NEG_PAD1") (class "Default")
      (node (ref "U$5") (pin "P$1") (pinfunction "0_P$1") (pintype "bidirectional"))
      (node (ref "U2") (pin "1") (pinfunction "OUTR_1") (pintype "bidirectional"))
      (node (ref "U2") (pin "2") (pinfunction "OUTG_2") (pintype "bidirectional"))
      (node (ref "U2") (pin "3") (pinfunction "OUTB_3") (pintype "bidirectional"))
    )
    (net (code "38") (name "NEG_PAD2") (class "Default")
      (node (ref "U$9") (pin "P$1") (pinfunction "0_P$1") (pintype "bidirectional"))
      (node (ref "U3") (pin "1") (pinfunction "OUTR_1") (pintype "bidirectional"))
      (node (ref "U3") (pin "2") (pinfunction "OUTG_2") (pintype "bidirectional"))
      (node (ref "U3") (pin "3") (pinfunction "OUTB_3") (pintype "bidirectional"))
    )
    (net (code "39") (name "NEG_PAD3") (class "Default")
      (node (ref "U$13") (pin "P$1") (pinfunction "0_P$1") (pintype "bidirectional"))
      (node (ref "U4") (pin "1") (pinfunction "OUTR_1") (pintype "bidirectional"))
      (node (ref "U4") (pin "2") (pinfunction "OUTG_2") (pintype "bidirectional"))
      (node (ref "U4") (pin "3") (pinfunction "OUTB_3") (pintype "bidirectional"))
    )
    (net (code "40") (name "NEG_PAD4") (class "Default")
      (node (ref "U$17") (pin "P$1") (pinfunction "0_P$1") (pintype "bidirectional"))
      (node (ref "U5") (pin "1") (pinfunction "OUTR_1") (pintype "bidirectional"))
      (node (ref "U5") (pin "2") (pinfunction "OUTG_2") (pintype "bidirectional"))
      (node (ref "U5") (pin "3") (pinfunction "OUTB_3") (pintype "bidirectional"))
    )
    (net (code "41") (name "NEG_PAD5") (class "Default")
      (node (ref "U$21") (pin "P$1") (pinfunction "0_P$1") (pintype "bidirectional"))
      (node (ref "U6") (pin "1") (pinfunction "OUTR_1") (pintype "bidirectional"))
      (node (ref "U6") (pin "2") (pinfunction "OUTG_2") (pintype "bidirectional"))
      (node (ref "U6") (pin "3") (pinfunction "OUTB_3") (pintype "bidirectional"))
    )
    (net (code "42") (name "NEG_PAD6") (class "Default")
      (node (ref "U$25") (pin "P$1") (pinfunction "0_P$1") (pintype "bidirectional"))
      (node (ref "U7") (pin "1") (pinfunction "OUTR_1") (pintype "bidirectional"))
      (node (ref "U7") (pin "2") (pinfunction "OUTG_2") (pintype "bidirectional"))
      (node (ref "U7") (pin "3") (pinfunction "OUTB_3") (pintype "bidirectional"))
    )
    (net (code "43") (name "NEG_PAD7") (class "Default")
      (node (ref "U$29") (pin "P$1") (pinfunction "0_P$1") (pintype "bidirectional"))
      (node (ref "U8") (pin "1") (pinfunction "OUTR_1") (pintype "bidirectional"))
      (node (ref "U8") (pin "2") (pinfunction "OUTG_2") (pintype "bidirectional"))
      (node (ref "U8") (pin "3") (pinfunction "OUTB_3") (pintype "bidirectional"))
    )
    (net (code "44") (name "NEG_PAD8") (class "Default")
      (node (ref "U$33") (pin "P$1") (pinfunction "0_P$1") (pintype "bidirectional"))
      (node (ref "U9") (pin "1") (pinfunction "OUTR_1") (pintype "bidirectional"))
      (node (ref "U9") (pin "2") (pinfunction "OUTG_2") (pintype "bidirectional"))
      (node (ref "U9") (pin "3") (pinfunction "OUTB_3") (pintype "bidirectional"))
    )
    (net (code "45") (name "NEG_PAD9") (class "Default")
      (node (ref "U$37") (pin "P$1") (pinfunction "0_P$1") (pintype "bidirectional"))
      (node (ref "U10") (pin "1") (pinfunction "OUTR_1") (pintype "bidirectional"))
      (node (ref "U10") (pin "2") (pinfunction "OUTG_2") (pintype "bidirectional"))
      (node (ref "U10") (pin "3") (pinfunction "OUTB_3") (pintype "bidirectional"))
    )
    (net (code "46") (name "NEG_PAD10") (class "Default")
      (node (ref "U$41") (pin "P$1") (pinfunction "0_P$1") (pintype "bidirectional"))
      (node (ref "U11") (pin "1") (pinfunction "OUTR_1") (pintype "bidirectional"))
      (node (ref "U11") (pin "2") (pinfunction "OUTG_2") (pintype "bidirectional"))
      (node (ref "U11") (pin "3") (pinfunction "OUTB_3") (pintype "bidirectional"))
    )
    (net (code "47") (name "NEG_PAD11") (class "Default")
      (node (ref "U$45") (pin "P$1") (pinfunction "0_P$1") (pintype "bidirectional"))
      (node (ref "U12") (pin "1") (pinfunction "OUTR_1") (pintype "bidirectional"))
      (node (ref "U12") (pin "2") (pinfunction "OUTG_2") (pintype "bidirectional"))
      (node (ref "U12") (pin "3") (pinfunction "OUTB_3") (pintype "bidirectional"))
    )
    (net (code "48") (name "NEG_PAD12") (class "Default")
      (node (ref "U$49") (pin "P$1") (pinfunction "0_P$1") (pintype "bidirectional"))
      (node (ref "U13") (pin "1") (pinfunction "OUTR_1") (pintype "bidirectional"))
      (node (ref "U13") (pin "2") (pinfunction "OUTG_2") (pintype "bidirectional"))
      (node (ref "U13") (pin "3") (pinfunction "OUTB_3") (pintype "bidirectional"))
    )
    (net (code "49") (name "NEG_PAD13") (class "Default")
      (node (ref "U$53") (pin "P$1") (pinfunction "0_P$1") (pintype "bidirectional"))
      (node (ref "U14") (pin "1") (pinfunction "OUTR_1") (pintype "bidirectional"))
      (node (ref "U14") (pin "2") (pinfunction "OUTG_2") (pintype "bidirectional"))
      (node (ref "U14") (pin "3") (pinfunction "OUTB_3") (pintype "bidirectional"))
    )
    (net (code "50") (name "NEG_PAD14") (class "Default")
      (node (ref "U$57") (pin "P$1") (pinfunction "0_P$1") (pintype "bidirectional"))
      (node (ref "U15") (pin "1") (pinfunction "OUTR_1") (pintype "bidirectional"))
      (node (ref "U15") (pin "2") (pinfunction "OUTG_2") (pintype "bidirectional"))
      (node (ref "U15") (pin "3") (pinfunction "OUTB_3") (pintype "bidirectional"))
    )
    (net (code "51") (name "NEG_PAD15") (class "Default")
      (node (ref "U$61") (pin "P$1") (pinfunction "0_P$1") (pintype "bidirectional"))
      (node (ref "U16") (pin "1") (pinfunction "OUTR_1") (pintype "bidirectional"))
      (node (ref "U16") (pin "2") (pinfunction "OUTG_2") (pintype "bidirectional"))
      (node (ref "U16") (pin "3") (pinfunction "OUTB_3") (pintype "bidirectional"))
    )
    (net (code "52") (name "NEG_PAD16") (class "Default")
      (node (ref "U$65") (pin "P$1") (pinfunction "0_P$1") (pintype "bidirectional"))
      (node (ref "U17") (pin "1") (pinfunction "OUTR_1") (pintype "bidirectional"))
      (node (ref "U17") (pin "2") (pinfunction "OUTG_2") (pintype "bidirectional"))
      (node (ref "U17") (pin "3") (pinfunction "OUTB_3") (pintype "bidirectional"))
    )
    (net (code "53") (name "NEG_PAD17") (class "Default")
      (node (ref "U$69") (pin "P$1") (pinfunction "0_P$1") (pintype "bidirectional"))
      (node (ref "U18") (pin "1") (pinfunction "OUTR_1") (pintype "bidirectional"))
      (node (ref "U18") (pin "2") (pinfunction "OUTG_2") (pintype "bidirectional"))
      (node (ref "U18") (pin "3") (pinfunction "OUTB_3") (pintype "bidirectional"))
    )
    (net (code "54") (name "NEG_PAD18") (class "Default")
      (node (ref "U$73") (pin "P$1") (pinfunction "0_P$1") (pintype "bidirectional"))
      (node (ref "U19") (pin "1") (pinfunction "OUTR_1") (pintype "bidirectional"))
      (node (ref "U19") (pin "2") (pinfunction "OUTG_2") (pintype "bidirectional"))
      (node (ref "U19") (pin "3") (pinfunction "OUTB_3") (pintype "bidirectional"))
    )
    (net (code "55") (name "NEG_PAD19") (class "Default")
      (node (ref "U$77") (pin "P$1") (pinfunction "0_P$1") (pintype "bidirectional"))
      (node (ref "U20") (pin "1") (pinfunction "OUTR_1") (pintype "bidirectional"))
      (node (ref "U20") (pin "2") (pinfunction "OUTG_2") (pintype "bidirectional"))
      (node (ref "U20") (pin "3") (pinfunction "OUTB_3") (pintype "bidirectional"))
    )
    (net (code "56") (name "NEG_PAD20") (class "Default")
      (node (ref "U$81") (pin "P$1") (pinfunction "0_P$1") (pintype "bidirectional"))
      (node (ref "U21") (pin "1") (pinfunction "OUTR_1") (pintype "bidirectional"))
      (node (ref "U21") (pin "2") (pinfunction "OUTG_2") (pintype "bidirectional"))
      (node (ref "U21") (pin "3") (pinfunction "OUTB_3") (pintype "bidirectional"))
    )
    (net (code "57") (name "NEG_PAD21") (class "Default")
      (node (ref "U$85") (pin "P$1") (pinfunction "0_P$1") (pintype "bidirectional"))
      (node (ref "U22") (pin "1") (pinfunction "OUTR_1") (pintype "bidirectional"))
      (node (ref "U22") (pin "2") (pinfunction "OUTG_2") (pintype "bidirectional"))
      (node (ref "U22") (pin "3") (pinfunction "OUTB_3") (pintype "bidirectional"))
    )
    (net (code "58") (name "NEG_PAD22") (class "Default")
      (node (ref "U$89") (pin "P$1") (pinfunction "0_P$1") (pintype "bidirectional"))
      (node (ref "U23") (pin "1") (pinfunction "OUTR_1") (pintype "bidirectional"))
      (node (ref "U23") (pin "2") (pinfunction "OUTG_2") (pintype "bidirectional"))
      (node (ref "U23") (pin "3") (pinfunction "OUTB_3") (pintype "bidirectional"))
    )
    (net (code "59") (name "NEG_PAD23") (class "Default")
      (node (ref "U$93") (pin "P$1") (pinfunction "0_P$1") (pintype "bidirectional"))
      (node (ref "U24") (pin "1") (pinfunction "OUTR_1") (pintype "bidirectional"))
      (node (ref "U24") (pin "2") (pinfunction "OUTG_2") (pintype "bidirectional"))
      (node (ref "U24") (pin "3") (pinfunction "OUTB_3") (pintype "bidirectional"))
    )
    (net (code "60") (name "NEG_PAD24") (class "Default")
      (node (ref "U$97") (pin "P$1") (pinfunction "0_P$1") (pintype "bidirectional"))
      (node (ref "U25") (pin "1") (pinfunction "OUTR_1") (pintype "bidirectional"))
      (node (ref "U25") (pin "2") (pinfunction "OUTG_2") (pintype "bidirectional"))
      (node (ref "U25") (pin "3") (pinfunction "OUTB_3") (pintype "bidirectional"))
    )
    (net (code "61") (name "NEG_PAD25") (class "Default")
      (node (ref "U$101") (pin "P$1") (pinfunction "0_P$1") (pintype "bidirectional"))
      (node (ref "U26") (pin "1") (pinfunction "OUTR_1") (pintype "bidirectional"))
      (node (ref "U26") (pin "2") (pinfunction "OUTG_2") (pintype "bidirectional"))
      (node (ref "U26") (pin "3") (pinfunction "OUTB_3") (pintype "bidirectional"))
    )
    (net (code "62") (name "NEG_PAD26") (class "Default")
      (node (ref "U$105") (pin "P$1") (pinfunction "0_P$1") (pintype "bidirectional"))
      (node (ref "U27") (pin "1") (pinfunction "OUTR_1") (pintype "bidirectional"))
      (node (ref "U27") (pin "2") (pinfunction "OUTG_2") (pintype "bidirectional"))
      (node (ref "U27") (pin "3") (pinfunction "OUTB_3") (pintype "bidirectional"))
    )
    (net (code "63") (name "NEG_PAD27") (class "Default")
      (node (ref "U$109") (pin "P$1") (pinfunction "0_P$1") (pintype "bidirectional"))
      (node (ref "U28") (pin "1") (pinfunction "OUTR_1") (pintype "bidirectional"))
      (node (ref "U28") (pin "2") (pinfunction "OUTG_2") (pintype "bidirectional"))
      (node (ref "U28") (pin "3") (pinfunction "OUTB_3") (pintype "bidirectional"))
    )
    (net (code "64") (name "NEG_PAD28") (class "Default")
      (node (ref "U$113") (pin "P$1") (pinfunction "0_P$1") (pintype "bidirectional"))
      (node (ref "U29") (pin "1") (pinfunction "OUTR_1") (pintype "bidirectional"))
      (node (ref "U29") (pin "2") (pinfunction "OUTG_2") (pintype "bidirectional"))
      (node (ref "U29") (pin "3") (pinfunction "OUTB_3") (pintype "bidirectional"))
    )
    (net (code "65") (name "NEG_PAD29") (class "Default")
      (node (ref "U$117") (pin "P$1") (pinfunction "0_P$1") (pintype "bidirectional"))
      (node (ref "U30") (pin "1") (pinfunction "OUTR_1") (pintype "bidirectional"))
      (node (ref "U30") (pin "2") (pinfunction "OUTG_2") (pintype "bidirectional"))
      (node (ref "U30") (pin "3") (pinfunction "OUTB_3") (pintype "bidirectional"))
    )
    (net (code "66") (name "NEG_PAD30") (class "Default")
      (node (ref "U$121") (pin "P$1") (pinfunction "0_P$1") (pintype "bidirectional"))
      (node (ref "U31") (pin "1") (pinfunction "OUTR_1") (pintype "bidirectional"))
      (node (ref "U31") (pin "2") (pinfunction "OUTG_2") (pintype "bidirectional"))
      (node (ref "U31") (pin "3") (pinfunction "OUTB_3") (pintype "bidirectional"))
    )
    (net (code "67") (name "NEG_PAD31") (class "Default")
      (node (ref "U$125") (pin "P$1") (pinfunction "0_P$1") (pintype "bidirectional"))
      (node (ref "U32") (pin "1") (pinfunction "OUTR_1") (pintype "bidirectional"))
      (node (ref "U32") (pin "2") (pinfunction "OUTG_2") (pintype "bidirectional"))
      (node (ref "U32") (pin "3") (pinfunction "OUTB_3") (pintype "bidirectional"))
    )
    (net (code "68") (name "Net-(U1-DIN)") (class "Default")
      (node (ref "R4") (pin "1") (pinfunction "1_1") (pintype "passive"))
      (node (ref "U1") (pin "5") (pinfunction "DIN_5") (pintype "bidirectional"))
    )
    (net (code "69") (name "Net-(U1-DO)") (class "Default")
      (node (ref "R5") (pin "2") (pinfunction "2_2") (pintype "passive"))
      (node (ref "U1") (pin "4") (pinfunction "DO_4") (pintype "bidirectional"))
    )
    (net (code "70") (name "Net-(U1-VDD)") (class "Default")
      (node (ref "R6") (pin "1") (pinfunction "1_1") (pintype "passive"))
      (node (ref "U1") (pin "8") (pinfunction "VDD_8") (pintype "bidirectional"))
    )
    (net (code "71") (name "Net-(U2-DIN)") (class "Default")
      (node (ref "R1") (pin "1") (pinfunction "1_1") (pintype "passive"))
      (node (ref "U2") (pin "5") (pinfunction "DIN_5") (pintype "bidirectional"))
    )
    (net (code "72") (name "Net-(U2-DO)") (class "Default")
      (node (ref "R2") (pin "2") (pinfunction "2_2") (pintype "passive"))
      (node (ref "U2") (pin "4") (pinfunction "DO_4") (pintype "bidirectional"))
    )
    (net (code "73") (name "Net-(U2-VDD)") (class "Default")
      (node (ref "R3") (pin "1") (pinfunction "1_1") (pintype "passive"))
      (node (ref "U2") (pin "8") (pinfunction "VDD_8") (pintype "bidirectional"))
    )
    (net (code "74") (name "Net-(U3-DIN)") (class "Default")
      (node (ref "R7") (pin "1") (pinfunction "1_1") (pintype "passive"))
      (node (ref "U3") (pin "5") (pinfunction "DIN_5") (pintype "bidirectional"))
    )
    (net (code "75") (name "Net-(U3-DO)") (class "Default")
      (node (ref "R8") (pin "2") (pinfunction "2_2") (pintype "passive"))
      (node (ref "U3") (pin "4") (pinfunction "DO_4") (pintype "bidirectional"))
    )
    (net (code "76") (name "Net-(U3-VDD)") (class "Default")
      (node (ref "R9") (pin "1") (pinfunction "1_1") (pintype "passive"))
      (node (ref "U3") (pin "8") (pinfunction "VDD_8") (pintype "bidirectional"))
    )
    (net (code "77") (name "Net-(U4-DIN)") (class "Default")
      (node (ref "R10") (pin "1") (pinfunction "1_1") (pintype "passive"))
      (node (ref "U4") (pin "5") (pinfunction "DIN_5") (pintype "bidirectional"))
    )
    (net (code "78") (name "Net-(U4-DO)") (class "Default")
      (node (ref "R11") (pin "2") (pinfunction "2_2") (pintype "passive"))
      (node (ref "U4") (pin "4") (pinfunction "DO_4") (pintype "bidirectional"))
    )
    (net (code "79") (name "Net-(U4-VDD)") (class "Default")
      (node (ref "R12") (pin "1") (pinfunction "1_1") (pintype "passive"))
      (node (ref "U4") (pin "8") (pinfunction "VDD_8") (pintype "bidirectional"))
    )
    (net (code "80") (name "Net-(U5-DIN)") (class "Default")
      (node (ref "R13") (pin "1") (pinfunction "1_1") (pintype "passive"))
      (node (ref "U5") (pin "5") (pinfunction "DIN_5") (pintype "bidirectional"))
    )
    (net (code "81") (name "Net-(U5-DO)") (class "Default")
      (node (ref "R14") (pin "2") (pinfunction "2_2") (pintype "passive"))
      (node (ref "U5") (pin "4") (pinfunction "DO_4") (pintype "bidirectional"))
    )
    (net (code "82") (name "Net-(U5-VDD)") (class "Default")
      (node (ref "R15") (pin "1") (pinfunction "1_1") (pintype "passive"))
      (node (ref "U5") (pin "8") (pinfunction "VDD_8") (pintype "bidirectional"))
    )
    (net (code "83") (name "Net-(U6-DIN)") (class "Default")
      (node (ref "R16") (pin "1") (pinfunction "1_1") (pintype "passive"))
      (node (ref "U6") (pin "5") (pinfunction "DIN_5") (pintype "bidirectional"))
    )
    (net (code "84") (name "Net-(U6-DO)") (class "Default")
      (node (ref "R17") (pin "2") (pinfunction "2_2") (pintype "passive"))
      (node (ref "U6") (pin "4") (pinfunction "DO_4") (pintype "bidirectional"))
    )
    (net (code "85") (name "Net-(U6-VDD)") (class "Default")
      (node (ref "R18") (pin "1") (pinfunction "1_1") (pintype "passive"))
      (node (ref "U6") (pin "8") (pinfunction "VDD_8") (pintype "bidirectional"))
    )
    (net (code "86") (name "Net-(U7-DIN)") (class "Default")
      (node (ref "R19") (pin "1") (pinfunction "1_1") (pintype "passive"))
      (node (ref "U7") (pin "5") (pinfunction "DIN_5") (pintype "bidirectional"))
    )
    (net (code "87") (name "Net-(U7-DO)") (class "Default")
      (node (ref "R20") (pin "2") (pinfunction "2_2") (pintype "passive"))
      (node (ref "U7") (pin "4") (pinfunction "DO_4") (pintype "bidirectional"))
    )
    (net (code "88") (name "Net-(U7-VDD)") (class "Default")
      (node (ref "R21") (pin "1") (pinfunction "1_1") (pintype "passive"))
      (node (ref "U7") (pin "8") (pinfunction "VDD_8") (pintype "bidirectional"))
    )
    (net (code "89") (name "Net-(U8-DIN)") (class "Default")
      (node (ref "R22") (pin "1") (pinfunction "1_1") (pintype "passive"))
      (node (ref "U8") (pin "5") (pinfunction "DIN_5") (pintype "bidirectional"))
    )
    (net (code "90") (name "Net-(U8-DO)") (class "Default")
      (node (ref "R23") (pin "2") (pinfunction "2_2") (pintype "passive"))
      (node (ref "U8") (pin "4") (pinfunction "DO_4") (pintype "bidirectional"))
    )
    (net (code "91") (name "Net-(U8-VDD)") (class "Default")
      (node (ref "R24") (pin "1") (pinfunction "1_1") (pintype "passive"))
      (node (ref "U8") (pin "8") (pinfunction "VDD_8") (pintype "bidirectional"))
    )
    (net (code "92") (name "Net-(U9-DIN)") (class "Default")
      (node (ref "R25") (pin "1") (pinfunction "1_1") (pintype "passive"))
      (node (ref "U9") (pin "5") (pinfunction "DIN_5") (pintype "bidirectional"))
    )
    (net (code "93") (name "Net-(U9-DO)") (class "Default")
      (node (ref "R26") (pin "2") (pinfunction "2_2") (pintype "passive"))
      (node (ref "U9") (pin "4") (pinfunction "DO_4") (pintype "bidirectional"))
    )
    (net (code "94") (name "Net-(U9-VDD)") (class "Default")
      (node (ref "R27") (pin "1") (pinfunction "1_1") (pintype "passive"))
      (node (ref "U9") (pin "8") (pinfunction "VDD_8") (pintype "bidirectional"))
    )
    (net (code "95") (name "Net-(U10-DIN)") (class "Default")
      (node (ref "R28") (pin "1") (pinfunction "1_1") (pintype "passive"))
      (node (ref "U10") (pin "5") (pinfunction "DIN_5") (pintype "bidirectional"))
    )
    (net (code "96") (name "Net-(U10-DO)") (class "Default")
      (node (ref "R29") (pin "2") (pinfunction "2_2") (pintype "passive"))
      (node (ref "U10") (pin "4") (pinfunction "DO_4") (pintype "bidirectional"))
    )
    (net (code "97") (name "Net-(U10-VDD)") (class "Default")
      (node (ref "R30") (pin "1") (pinfunction "1_1") (pintype "passive"))
      (node (ref "U10") (pin "8") (pinfunction "VDD_8") (pintype "bidirectional"))
    )
    (net (code "98") (name "Net-(U11-DIN)") (class "Default")
      (node (ref "R31") (pin "1") (pinfunction "1_1") (pintype "passive"))
      (node (ref "U11") (pin "5") (pinfunction "DIN_5") (pintype "bidirectional"))
    )
    (net (code "99") (name "Net-(U11-DO)") (class "Default")
      (node (ref "R32") (pin "2") (pinfunction "2_2") (pintype "passive"))
      (node (ref "U11") (pin "4") (pinfunction "DO_4") (pintype "bidirectional"))
    )
    (net (code "100") (name "Net-(U11-VDD)") (class "Default")
      (node (ref "R33") (pin "1") (pinfunction "1_1") (pintype "passive"))
      (node (ref "U11") (pin "8") (pinfunction "VDD_8") (pintype "bidirectional"))
    )
    (net (code "101") (name "Net-(U12-DIN)") (class "Default")
      (node (ref "R34") (pin "1") (pinfunction "1_1") (pintype "passive"))
      (node (ref "U12") (pin "5") (pinfunction "DIN_5") (pintype "bidirectional"))
    )
    (net (code "102") (name "Net-(U12-DO)") (class "Default")
      (node (ref "R35") (pin "2") (pinfunction "2_2") (pintype "passive"))
      (node (ref "U12") (pin "4") (pinfunction "DO_4") (pintype "bidirectional"))
    )
    (net (code "103") (name "Net-(U12-VDD)") (class "Default")
      (node (ref "R36") (pin "1") (pinfunction "1_1") (pintype "passive"))
      (node (ref "U12") (pin "8") (pinfunction "VDD_8") (pintype "bidirectional"))
    )
    (net (code "104") (name "Net-(U13-DIN)") (class "Default")
      (node (ref "R37") (pin "1") (pinfunction "1_1") (pintype "passive"))
      (node (ref "U13") (pin "5") (pinfunction "DIN_5") (pintype "bidirectional"))
    )
    (net (code "105") (name "Net-(U13-DO)") (class "Default")
      (node (ref "R38") (pin "2") (pinfunction "2_2") (pintype "passive"))
      (node (ref "U13") (pin "4") (pinfunction "DO_4") (pintype "bidirectional"))
    )
    (net (code "106") (name "Net-(U13-VDD)") (class "Default")
      (node (ref "R39") (pin "1") (pinfunction "1_1") (pintype "passive"))
      (node (ref "U13") (pin "8") (pinfunction "VDD_8") (pintype "bidirectional"))
    )
    (net (code "107") (name "Net-(U14-DIN)") (class "Default")
      (node (ref "R40") (pin "1") (pinfunction "1_1") (pintype "passive"))
      (node (ref "U14") (pin "5") (pinfunction "DIN_5") (pintype "bidirectional"))
    )
    (net (code "108") (name "Net-(U14-DO)") (class "Default")
      (node (ref "R41") (pin "2") (pinfunction "2_2") (pintype "passive"))
      (node (ref "U14") (pin "4") (pinfunction "DO_4") (pintype "bidirectional"))
    )
    (net (code "109") (name "Net-(U14-VDD)") (class "Default")
      (node (ref "R42") (pin "1") (pinfunction "1_1") (pintype "passive"))
      (node (ref "U14") (pin "8") (pinfunction "VDD_8") (pintype "bidirectional"))
    )
    (net (code "110") (name "Net-(U15-DIN)") (class "Default")
      (node (ref "R43") (pin "1") (pinfunction "1_1") (pintype "passive"))
      (node (ref "U15") (pin "5") (pinfunction "DIN_5") (pintype "bidirectional"))
    )
    (net (code "111") (name "Net-(U15-DO)") (class "Default")
      (node (ref "R44") (pin "2") (pinfunction "2_2") (pintype "passive"))
      (node (ref "U15") (pin "4") (pinfunction "DO_4") (pintype "bidirectional"))
    )
    (net (code "112") (name "Net-(U15-VDD)") (class "Default")
      (node (ref "R45") (pin "1") (pinfunction "1_1") (pintype "passive"))
      (node (ref "U15") (pin "8") (pinfunction "VDD_8") (pintype "bidirectional"))
    )
    (net (code "113") (name "Net-(U16-DIN)") (class "Default")
      (node (ref "R46") (pin "1") (pinfunction "1_1") (pintype "passive"))
      (node (ref "U16") (pin "5") (pinfunction "DIN_5") (pintype "bidirectional"))
    )
    (net (code "114") (name "Net-(U16-DO)") (class "Default")
      (node (ref "R47") (pin "2") (pinfunction "2_2") (pintype "passive"))
      (node (ref "U16") (pin "4") (pinfunction "DO_4") (pintype "bidirectional"))
    )
    (net (code "115") (name "Net-(U16-VDD)") (class "Default")
      (node (ref "R48") (pin "1") (pinfunction "1_1") (pintype "passive"))
      (node (ref "U16") (pin "8") (pinfunction "VDD_8") (pintype "bidirectional"))
    )
    (net (code "116") (name "Net-(U17-DIN)") (class "Default")
      (node (ref "R49") (pin "1") (pinfunction "1_1") (pintype "passive"))
      (node (ref "U17") (pin "5") (pinfunction "DIN_5") (pintype "bidirectional"))
    )
    (net (code "117") (name "Net-(U17-DO)") (class "Default")
      (node (ref "R50") (pin "2") (pinfunction "2_2") (pintype "passive"))
      (node (ref "U17") (pin "4") (pinfunction "DO_4") (pintype "bidirectional"))
    )
    (net (code "118") (name "Net-(U17-VDD)") (class "Default")
      (node (ref "R51") (pin "1") (pinfunction "1_1") (pintype "passive"))
      (node (ref "U17") (pin "8") (pinfunction "VDD_8") (pintype "bidirectional"))
    )
    (net (code "119") (name "Net-(U18-DIN)") (class "Default")
      (node (ref "R52") (pin "1") (pinfunction "1_1") (pintype "passive"))
      (node (ref "U18") (pin "5") (pinfunction "DIN_5") (pintype "bidirectional"))
    )
    (net (code "120") (name "Net-(U18-DO)") (class "Default")
      (node (ref "R53") (pin "2") (pinfunction "2_2") (pintype "passive"))
      (node (ref "U18") (pin "4") (pinfunction "DO_4") (pintype "bidirectional"))
    )
    (net (code "121") (name "Net-(U18-VDD)") (class "Default")
      (node (ref "R54") (pin "1") (pinfunction "1_1") (pintype "passive"))
      (node (ref "U18") (pin "8") (pinfunction "VDD_8") (pintype "bidirectional"))
    )
    (net (code "122") (name "Net-(U19-DIN)") (class "Default")
      (node (ref "R55") (pin "1") (pinfunction "1_1") (pintype "passive"))
      (node (ref "U19") (pin "5") (pinfunction "DIN_5") (pintype "bidirectional"))
    )
    (net (code "123") (name "Net-(U19-DO)") (class "Default")
      (node (ref "R56") (pin "2") (pinfunction "2_2") (pintype "passive"))
      (node (ref "U19") (pin "4") (pinfunction "DO_4") (pintype "bidirectional"))
    )
    (net (code "124") (name "Net-(U19-VDD)") (class "Default")
      (node (ref "R57") (pin "1") (pinfunction "1_1") (pintype "passive"))
      (node (ref "U19") (pin "8") (pinfunction "VDD_8") (pintype "bidirectional"))
    )
    (net (code "125") (name "Net-(U20-DIN)") (class "Default")
      (node (ref "R58") (pin "1") (pinfunction "1_1") (pintype "passive"))
      (node (ref "U20") (pin "5") (pinfunction "DIN_5") (pintype "bidirectional"))
    )
    (net (code "126") (name "Net-(U20-DO)") (class "Default")
      (node (ref "R59") (pin "2") (pinfunction "2_2") (pintype "passive"))
      (node (ref "U20") (pin "4") (pinfunction "DO_4") (pintype "bidirectional"))
    )
    (net (code "127") (name "Net-(U20-VDD)") (class "Default")
      (node (ref "R60") (pin "1") (pinfunction "1_1") (pintype "passive"))
      (node (ref "U20") (pin "8") (pinfunction "VDD_8") (pintype "bidirectional"))
    )
    (net (code "128") (name "Net-(U21-DIN)") (class "Default")
      (node (ref "R61") (pin "1") (pinfunction "1_1") (pintype "passive"))
      (node (ref "U21") (pin "5") (pinfunction "DIN_5") (pintype "bidirectional"))
    )
    (net (code "129") (name "Net-(U21-DO)") (class "Default")
      (node (ref "R62") (pin "2") (pinfunction "2_2") (pintype "passive"))
      (node (ref "U21") (pin "4") (pinfunction "DO_4") (pintype "bidirectional"))
    )
    (net (code "130") (name "Net-(U21-VDD)") (class "Default")
      (node (ref "R63") (pin "1") (pinfunction "1_1") (pintype "passive"))
      (node (ref "U21") (pin "8") (pinfunction "VDD_8") (pintype "bidirectional"))
    )
    (net (code "131") (name "Net-(U22-DIN)") (class "Default")
      (node (ref "R64") (pin "1") (pinfunction "1_1") (pintype "passive"))
      (node (ref "U22") (pin "5") (pinfunction "DIN_5") (pintype "bidirectional"))
    )
    (net (code "132") (name "Net-(U22-DO)") (class "Default")
      (node (ref "R65") (pin "2") (pinfunction "2_2") (pintype "passive"))
      (node (ref "U22") (pin "4") (pinfunction "DO_4") (pintype "bidirectional"))
    )
    (net (code "133") (name "Net-(U22-VDD)") (class "Default")
      (node (ref "R66") (pin "1") (pinfunction "1_1") (pintype "passive"))
      (node (ref "U22") (pin "8") (pinfunction "VDD_8") (pintype "bidirectional"))
    )
    (net (code "134") (name "Net-(U23-DIN)") (class "Default")
      (node (ref "R67") (pin "1") (pinfunction "1_1") (pintype "passive"))
      (node (ref "U23") (pin "5") (pinfunction "DIN_5") (pintype "bidirectional"))
    )
    (net (code "135") (name "Net-(U23-DO)") (class "Default")
      (node (ref "R68") (pin "2") (pinfunction "2_2") (pintype "passive"))
      (node (ref "U23") (pin "4") (pinfunction "DO_4") (pintype "bidirectional"))
    )
    (net (code "136") (name "Net-(U23-VDD)") (class "Default")
      (node (ref "R69") (pin "1") (pinfunction "1_1") (pintype "passive"))
      (node (ref "U23") (pin "8") (pinfunction "VDD_8") (pintype "bidirectional"))
    )
    (net (code "137") (name "Net-(U24-DIN)") (class "Default")
      (node (ref "R70") (pin "1") (pinfunction "1_1") (pintype "passive"))
      (node (ref "U24") (pin "5") (pinfunction "DIN_5") (pintype "bidirectional"))
    )
    (net (code "138") (name "Net-(U24-DO)") (class "Default")
      (node (ref "R71") (pin "2") (pinfunction "2_2") (pintype "passive"))
      (node (ref "U24") (pin "4") (pinfunction "DO_4") (pintype "bidirectional"))
    )
    (net (code "139") (name "Net-(U24-VDD)") (class "Default")
      (node (ref "R72") (pin "1") (pinfunction "1_1") (pintype "passive"))
      (node (ref "U24") (pin "8") (pinfunction "VDD_8") (pintype "bidirectional"))
    )
    (net (code "140") (name "Net-(U25-DIN)") (class "Default")
      (node (ref "R73") (pin "1") (pinfunction "1_1") (pintype "passive"))
      (node (ref "U25") (pin "5") (pinfunction "DIN_5") (pintype "bidirectional"))
    )
    (net (code "141") (name "Net-(U25-DO)") (class "Default")
      (node (ref "R74") (pin "2") (pinfunction "2_2") (pintype "passive"))
      (node (ref "U25") (pin "4") (pinfunction "DO_4") (pintype "bidirectional"))
    )
    (net (code "142") (name "Net-(U25-VDD)") (class "Default")
      (node (ref "R75") (pin "1") (pinfunction "1_1") (pintype "passive"))
      (node (ref "U25") (pin "8") (pinfunction "VDD_8") (pintype "bidirectional"))
    )
    (net (code "143") (name "Net-(U26-DIN)") (class "Default")
      (node (ref "R76") (pin "1") (pinfunction "1_1") (pintype "passive"))
      (node (ref "U26") (pin "5") (pinfunction "DIN_5") (pintype "bidirectional"))
    )
    (net (code "144") (name "Net-(U26-DO)") (class "Default")
      (node (ref "R77") (pin "2") (pinfunction "2_2") (pintype "passive"))
      (node (ref "U26") (pin "4") (pinfunction "DO_4") (pintype "bidirectional"))
    )
    (net (code "145") (name "Net-(U26-VDD)") (class "Default")
      (node (ref "R78") (pin "1") (pinfunction "1_1") (pintype "passive"))
      (node (ref "U26") (pin "8") (pinfunction "VDD_8") (pintype "bidirectional"))
    )
    (net (code "146") (name "Net-(U27-DIN)") (class "Default")
      (node (ref "R79") (pin "1") (pinfunction "1_1") (pintype "passive"))
      (node (ref "U27") (pin "5") (pinfunction "DIN_5") (pintype "bidirectional"))
    )
    (net (code "147") (name "Net-(U27-DO)") (class "Default")
      (node (ref "R80") (pin "2") (pinfunction "2_2") (pintype "passive"))
      (node (ref "U27") (pin "4") (pinfunction "DO_4") (pintype "bidirectional"))
    )
    (net (code "148") (name "Net-(U27-VDD)") (class "Default")
      (node (ref "R81") (pin "1") (pinfunction "1_1") (pintype "passive"))
      (node (ref "U27") (pin "8") (pinfunction "VDD_8") (pintype "bidirectional"))
    )
    (net (code "149") (name "Net-(U28-DIN)") (class "Default")
      (node (ref "R82") (pin "1") (pinfunction "1_1") (pintype "passive"))
      (node (ref "U28") (pin "5") (pinfunction "DIN_5") (pintype "bidirectional"))
    )
    (net (code "150") (name "Net-(U28-DO)") (class "Default")
      (node (ref "R83") (pin "2") (pinfunction "2_2") (pintype "passive"))
      (node (ref "U28") (pin "4") (pinfunction "DO_4") (pintype "bidirectional"))
    )
    (net (code "151") (name "Net-(U28-VDD)") (class "Default")
      (node (ref "R84") (pin "1") (pinfunction "1_1") (pintype "passive"))
      (node (ref "U28") (pin "8") (pinfunction "VDD_8") (pintype "bidirectional"))
    )
    (net (code "152") (name "Net-(U29-DIN)") (class "Default")
      (node (ref "R85") (pin "1") (pinfunction "1_1") (pintype "passive"))
      (node (ref "U29") (pin "5") (pinfunction "DIN_5") (pintype "bidirectional"))
    )
    (net (code "153") (name "Net-(U29-DO)") (class "Default")
      (node (ref "R86") (pin "2") (pinfunction "2_2") (pintype "passive"))
      (node (ref "U29") (pin "4") (pinfunction "DO_4") (pintype "bidirectional"))
    )
    (net (code "154") (name "Net-(U29-VDD)") (class "Default")
      (node (ref "R87") (pin "1") (pinfunction "1_1") (pintype "passive"))
      (node (ref "U29") (pin "8") (pinfunction "VDD_8") (pintype "bidirectional"))
    )
    (net (code "155") (name "Net-(U30-DIN)") (class "Default")
      (node (ref "R88") (pin "1") (pinfunction "1_1") (pintype "passive"))
      (node (ref "U30") (pin "5") (pinfunction "DIN_5") (pintype "bidirectional"))
    )
    (net (code "156") (name "Net-(U30-DO)") (class "Default")
      (node (ref "R89") (pin "2") (pinfunction "2_2") (pintype "passive"))
      (node (ref "U30") (pin "4") (pinfunction "DO_4") (pintype "bidirectional"))
    )
    (net (code "157") (name "Net-(U30-VDD)") (class "Default")
      (node (ref "R90") (pin "1") (pinfunction "1_1") (pintype "passive"))
      (node (ref "U30") (pin "8") (pinfunction "VDD_8") (pintype "bidirectional"))
    )
    (net (code "158") (name "Net-(U31-DIN)") (class "Default")
      (node (ref "R91") (pin "1") (pinfunction "1_1") (pintype "passive"))
      (node (ref "U31") (pin "5") (pinfunction "DIN_5") (pintype "bidirectional"))
    )
    (net (code "159") (name "Net-(U31-DO)") (class "Default")
      (node (ref "R92") (pin "2") (pinfunction "2_2") (pintype "passive"))
      (node (ref "U31") (pin "4") (pinfunction "DO_4") (pintype "bidirectional"))
    )
    (net (code "160") (name "Net-(U31-VDD)") (class "Default")
      (node (ref "R93") (pin "1") (pinfunction "1_1") (pintype "passive"))
      (node (ref "U31") (pin "8") (pinfunction "VDD_8") (pintype "bidirectional"))
    )
    (net (code "161") (name "Net-(U32-DIN)") (class "Default")
      (node (ref "R94") (pin "1") (pinfunction "1_1") (pintype "passive"))
      (node (ref "U32") (pin "5") (pinfunction "DIN_5") (pintype "bidirectional"))
    )
    (net (code "162") (name "Net-(U32-DO)") (class "Default")
      (node (ref "R95") (pin "2") (pinfunction "2_2") (pintype "passive"))
      (node (ref "U32") (pin "4") (pinfunction "DO_4") (pintype "bidirectional"))
    )
    (net (code "163") (name "Net-(U32-VDD)") (class "Default")
      (node (ref "R96") (pin "1") (pinfunction "1_1") (pintype "passive"))
      (node (ref "U32") (pin "8") (pinfunction "VDD_8") (pintype "bidirectional"))
    )
    (net (code "164") (name "VCC") (class "Default")
      (node (ref "C1") (pin "1") (pinfunction "1_1") (pintype "passive"))
      (node (ref "C10") (pin "1") (pinfunction "1_1") (pintype "passive"))
      (node (ref "C11") (pin "1") (pinfunction "1_1") (pintype "passive"))
      (node (ref "C12") (pin "1") (pinfunction "1_1") (pintype "passive"))
      (node (ref "C13") (pin "1") (pinfunction "1_1") (pintype "passive"))
      (node (ref "C14") (pin "1") (pinfunction "1_1") (pintype "passive"))
      (node (ref "C15") (pin "1") (pinfunction "1_1") (pintype "passive"))
      (node (ref "C16") (pin "1") (pinfunction "1_1") (pintype "passive"))
      (node (ref "C17") (pin "1") (pinfunction "1_1") (pintype "passive"))
      (node (ref "C18") (pin "1") (pinfunction "1_1") (pintype "passive"))
      (node (ref "C19") (pin "1") (pinfunction "1_1") (pintype "passive"))
      (node (ref "C2") (pin "1") (pinfunction "1_1") (pintype "passive"))
      (node (ref "C20") (pin "1") (pinfunction "1_1") (pintype "passive"))
      (node (ref "C21") (pin "1") (pinfunction "1_1") (pintype "passive"))
      (node (ref "C22") (pin "1") (pinfunction "1_1") (pintype "passive"))
      (node (ref "C23") (pin "1") (pinfunction "1_1") (pintype "passive"))
      (node (ref "C24") (pin "1") (pinfunction "1_1") (pintype "passive"))
      (node (ref "C25") (pin "1") (pinfunction "1_1") (pintype "passive"))
      (node (ref "C26") (pin "1") (pinfunction "1_1") (pintype "passive"))
      (node (ref "C27") (pin "1") (pinfunction "1_1") (pintype "passive"))
      (node (ref "C28") (pin "1") (pinfunction "1_1") (pintype "passive"))
      (node (ref "C29") (pin "1") (pinfunction "1_1") (pintype "passive"))
      (node (ref "C3") (pin "1") (pinfunction "1_1") (pintype "passive"))
      (node (ref "C30") (pin "1") (pinfunction "1_1") (pintype "passive"))
      (node (ref "C31") (pin "1") (pinfunction "1_1") (pintype "passive"))
      (node (ref "C32") (pin "1") (pinfunction "1_1") (pintype "passive"))
      (node (ref "C4") (pin "1") (pinfunction "1_1") (pintype "passive"))
      (node (ref "C5") (pin "1") (pinfunction "1_1") (pintype "passive"))
      (node (ref "C6") (pin "1") (pinfunction "1_1") (pintype "passive"))
      (node (ref "C7") (pin "1") (pinfunction "1_1") (pintype "passive"))
      (node (ref "C8") (pin "1") (pinfunction "1_1") (pintype "passive"))
      (node (ref "C9") (pin "1") (pinfunction "1_1") (pintype "passive"))
      (node (ref "R12") (pin "2") (pinfunction "2_2") (pintype "passive"))
      (node (ref "R15") (pin "2") (pinfunction "2_2") (pintype "passive"))
      (node (ref "R18") (pin "2") (pinfunction "2_2") (pintype "passive"))
      (node (ref "R21") (pin "2") (pinfunction "2_2") (pintype "passive"))
      (node (ref "R24") (pin "2") (pinfunction "2_2") (pintype "passive"))
      (node (ref "R27") (pin "2") (pinfunction "2_2") (pintype "passive"))
      (node (ref "R3") (pin "2") (pinfunction "2_2") (pintype "passive"))
      (node (ref "R30") (pin "2") (pinfunction "2_2") (pintype "passive"))
      (node (ref "R33") (pin "2") (pinfunction "2_2") (pintype "passive"))
      (node (ref "R36") (pin "2") (pinfunction "2_2") (pintype "passive"))
      (node (ref "R39") (pin "2") (pinfunction "2_2") (pintype "passive"))
      (node (ref "R42") (pin "2") (pinfunction "2_2") (pintype "passive"))
      (node (ref "R45") (pin "2") (pinfunction "2_2") (pintype "passive"))
      (node (ref "R48") (pin "2") (pinfunction "2_2") (pintype "passive"))
      (node (ref "R51") (pin "2") (pinfunction "2_2") (pintype "passive"))
      (node (ref "R54") (pin "2") (pinfunction "2_2") (pintype "passive"))
      (node (ref "R57") (pin "2") (pinfunction "2_2") (pintype "passive"))
      (node (ref "R6") (pin "2") (pinfunction "2_2") (pintype "passive"))
      (node (ref "R60") (pin "2") (pinfunction "2_2") (pintype "passive"))
      (node (ref "R63") (pin "2") (pinfunction "2_2") (pintype "passive"))
      (node (ref "R66") (pin "2") (pinfunction "2_2") (pintype "passive"))
      (node (ref "R69") (pin "2") (pinfunction "2_2") (pintype "passive"))
      (node (ref "R72") (pin "2") (pinfunction "2_2") (pintype "passive"))
      (node (ref "R75") (pin "2") (pinfunction "2_2") (pintype "passive"))
      (node (ref "R78") (pin "2") (pinfunction "2_2") (pintype "passive"))
      (node (ref "R81") (pin "2") (pinfunction "2_2") (pintype "passive"))
      (node (ref "R84") (pin "2") (pinfunction "2_2") (pintype "passive"))
      (node (ref "R87") (pin "2") (pinfunction "2_2") (pintype "passive"))
      (node (ref "R9") (pin "2") (pinfunction "2_2") (pintype "passive"))
      (node (ref "R90") (pin "2") (pinfunction "2_2") (pintype "passive"))
      (node (ref "R93") (pin "2") (pinfunction "2_2") (pintype "passive"))
      (node (ref "R96") (pin "2") (pinfunction "2_2") (pintype "passive"))
      (node (ref "U$1") (pin "P$2") (pinfunction "1_P$2") (pintype "bidirectional"))
      (node (ref "U$100") (pin "P$4") (pinfunction "P$4_P$4") (pintype "bidirectional"))
      (node (ref "U$101") (pin "P$2") (pinfunction "1_P$2") (pintype "bidirectional"))
      (node (ref "U$103") (pin "P$4") (pinfunction "P$4_P$4") (pintype "bidirectional"))
      (node (ref "U$104") (pin "P$4") (pinfunction "P$4_P$4") (pintype "bidirectional"))
      (node (ref "U$105") (pin "P$2") (pinfunction "1_P$2") (pintype "bidirectional"))
      (node (ref "U$107") (pin "P$4") (pinfunction "P$4_P$4") (pintype "bidirectional"))
      (node (ref "U$108") (pin "P$4") (pinfunction "P$4_P$4") (pintype "bidirectional"))
      (node (ref "U$109") (pin "P$2") (pinfunction "1_P$2") (pintype "bidirectional"))
      (node (ref "U$11") (pin "P$4") (pinfunction "P$4_P$4") (pintype "bidirectional"))
      (node (ref "U$111") (pin "P$4") (pinfunction "P$4_P$4") (pintype "bidirectional"))
      (node (ref "U$112") (pin "P$4") (pinfunction "P$4_P$4") (pintype "bidirectional"))
      (node (ref "U$113") (pin "P$2") (pinfunction "1_P$2") (pintype "bidirectional"))
      (node (ref "U$115") (pin "P$4") (pinfunction "P$4_P$4") (pintype "bidirectional"))
      (node (ref "U$116") (pin "P$4") (pinfunction "P$4_P$4") (pintype "bidirectional"))
      (node (ref "U$117") (pin "P$2") (pinfunction "1_P$2") (pintype "bidirectional"))
      (node (ref "U$119") (pin "P$4") (pinfunction "P$4_P$4") (pintype "bidirectional"))
      (node (ref "U$12") (pin "P$4") (pinfunction "P$4_P$4") (pintype "bidirectional"))
      (node (ref "U$120") (pin "P$4") (pinfunction "P$4_P$4") (pintype "bidirectional"))
      (node (ref "U$121") (pin "P$2") (pinfunction "1_P$2") (pintype "bidirectional"))
      (node (ref "U$123") (pin "P$4") (pinfunction "P$4_P$4") (pintype "bidirectional"))
      (node (ref "U$124") (pin "P$4") (pinfunction "P$4_P$4") (pintype "bidirectional"))
      (node (ref "U$125") (pin "P$2") (pinfunction "1_P$2") (pintype "bidirectional"))
      (node (ref "U$127") (pin "P$4") (pinfunction "P$4_P$4") (pintype "bidirectional"))
      (node (ref "U$128") (pin "P$4") (pinfunction "P$4_P$4") (pintype "bidirectional"))
      (node (ref "U$13") (pin "P$2") (pinfunction "1_P$2") (pintype "bidirectional"))
      (node (ref "U$15") (pin "P$4") (pinfunction "P$4_P$4") (pintype "bidirectional"))
      (node (ref "U$16") (pin "P$4") (pinfunction "P$4_P$4") (pintype "bidirectional"))
      (node (ref "U$17") (pin "P$2") (pinfunction "1_P$2") (pintype "bidirectional"))
      (node (ref "U$19") (pin "P$4") (pinfunction "P$4_P$4") (pintype "bidirectional"))
      (node (ref "U$20") (pin "P$4") (pinfunction "P$4_P$4") (pintype "bidirectional"))
      (node (ref "U$21") (pin "P$2") (pinfunction "1_P$2") (pintype "bidirectional"))
      (node (ref "U$23") (pin "P$4") (pinfunction "P$4_P$4") (pintype "bidirectional"))
      (node (ref "U$24") (pin "P$4") (pinfunction "P$4_P$4") (pintype "bidirectional"))
      (node (ref "U$25") (pin "P$2") (pinfunction "1_P$2") (pintype "bidirectional"))
      (node (ref "U$27") (pin "P$4") (pinfunction "P$4_P$4") (pintype "bidirectional"))
      (node (ref "U$28") (pin "P$4") (pinfunction "P$4_P$4") (pintype "bidirectional"))
      (node (ref "U$29") (pin "P$2") (pinfunction "1_P$2") (pintype "bidirectional"))
      (node (ref "U$3") (pin "P$4") (pinfunction "P$4_P$4") (pintype "bidirectional"))
      (node (ref "U$31") (pin "P$4") (pinfunction "P$4_P$4") (pintype "bidirectional"))
      (node (ref "U$32") (pin "P$4") (pinfunction "P$4_P$4") (pintype "bidirectional"))
      (node (ref "U$33") (pin "P$2") (pinfunction "1_P$2") (pintype "bidirectional"))
      (node (ref "U$35") (pin "P$4") (pinfunction "P$4_P$4") (pintype "bidirectional"))
      (node (ref "U$36") (pin "P$4") (pinfunction "P$4_P$4") (pintype "bidirectional"))
      (node (ref "U$37") (pin "P$2") (pinfunction "1_P$2") (pintype "bidirectional"))
      (node (ref "U$39") (pin "P$4") (pinfunction "P$4_P$4") (pintype "bidirectional"))
      (node (ref "U$4") (pin "P$4") (pinfunction "P$4_P$4") (pintype "bidirectional"))
      (node (ref "U$40") (pin "P$4") (pinfunction "P$4_P$4") (pintype "bidirectional"))
      (node (ref "U$41") (pin "P$2") (pinfunction "1_P$2") (pintype "bidirectional"))
      (node (ref "U$43") (pin "P$4") (pinfunction "P$4_P$4") (pintype "bidirectional"))
      (node (ref "U$44") (pin "P$4") (pinfunction "P$4_P$4") (pintype "bidirectional"))
      (node (ref "U$45") (pin "P$2") (pinfunction "1_P$2") (pintype "bidirectional"))
      (node (ref "U$47") (pin "P$4") (pinfunction "P$4_P$4") (pintype "bidirectional"))
      (node (ref "U$48") (pin "P$4") (pinfunction "P$4_P$4") (pintype "bidirectional"))
      (node (ref "U$49") (pin "P$2") (pinfunction "1_P$2") (pintype "bidirectional"))
      (node (ref "U$5") (pin "P$2") (pinfunction "1_P$2") (pintype "bidirectional"))
      (node (ref "U$51") (pin "P$4") (pinfunction "P$4_P$4") (pintype "bidirectional"))
      (node (ref "U$52") (pin "P$4") (pinfunction "P$4_P$4") (pintype "bidirectional"))
      (node (ref "U$53") (pin "P$2") (pinfunction "1_P$2") (pintype "bidirectional"))
      (node (ref "U$55") (pin "P$4") (pinfunction "P$4_P$4") (pintype "bidirectional"))
      (node (ref "U$56") (pin "P$4") (pinfunction "P$4_P$4") (pintype "bidirectional"))
      (node (ref "U$57") (pin "P$2") (pinfunction "1_P$2") (pintype "bidirectional"))
      (node (ref "U$59") (pin "P$4") (pinfunction "P$4_P$4") (pintype "bidirectional"))
      (node (ref "U$60") (pin "P$4") (pinfunction "P$4_P$4") (pintype "bidirectional"))
      (node (ref "U$61") (pin "P$2") (pinfunction "1_P$2") (pintype "bidirectional"))
      (node (ref "U$63") (pin "P$4") (pinfunction "P$4_P$4") (pintype "bidirectional"))
      (node (ref "U$64") (pin "P$4") (pinfunction "P$4_P$4") (pintype "bidirectional"))
      (node (ref "U$65") (pin "P$2") (pinfunction "1_P$2") (pintype "bidirectional"))
      (node (ref "U$67") (pin "P$4") (pinfunction "P$4_P$4") (pintype "bidirectional"))
      (node (ref "U$68") (pin "P$4") (pinfunction "P$4_P$4") (pintype "bidirectional"))
      (node (ref "U$69") (pin "P$2") (pinfunction "1_P$2") (pintype "bidirectional"))
      (node (ref "U$7") (pin "P$4") (pinfunction "P$4_P$4") (pintype "bidirectional"))
      (node (ref "U$71") (pin "P$4") (pinfunction "P$4_P$4") (pintype "bidirectional"))
      (node (ref "U$72") (pin "P$4") (pinfunction "P$4_P$4") (pintype "bidirectional"))
      (node (ref "U$73") (pin "P$2") (pinfunction "1_P$2") (pintype "bidirectional"))
      (node (ref "U$75") (pin "P$4") (pinfunction "P$4_P$4") (pintype "bidirectional"))
      (node (ref "U$76") (pin "P$4") (pinfunction "P$4_P$4") (pintype "bidirectional"))
      (node (ref "U$77") (pin "P$2") (pinfunction "1_P$2") (pintype "bidirectional"))
      (node (ref "U$79") (pin "P$4") (pinfunction "P$4_P$4") (pintype "bidirectional"))
      (node (ref "U$8") (pin "P$4") (pinfunction "P$4_P$4") (pintype "bidirectional"))
      (node (ref "U$80") (pin "P$4") (pinfunction "P$4_P$4") (pintype "bidirectional"))
      (node (ref "U$81") (pin "P$2") (pinfunction "1_P$2") (pintype "bidirectional"))
      (node (ref "U$83") (pin "P$4") (pinfunction "P$4_P$4") (pintype "bidirectional"))
      (node (ref "U$84") (pin "P$4") (pinfunction "P$4_P$4") (pintype "bidirectional"))
      (node (ref "U$85") (pin "P$2") (pinfunction "1_P$2") (pintype "bidirectional"))
      (node (ref "U$87") (pin "P$4") (pinfunction "P$4_P$4") (pintype "bidirectional"))
      (node (ref "U$88") (pin "P$4") (pinfunction "P$4_P$4") (pintype "bidirectional"))
      (node (ref "U$89") (pin "P$2") (pinfunction "1_P$2") (pintype "bidirectional"))
      (node (ref "U$9") (pin "P$2") (pinfunction "1_P$2") (pintype "bidirectional"))
      (node (ref "U$91") (pin "P$4") (pinfunction "P$4_P$4") (pintype "bidirectional"))
      (node (ref "U$92") (pin "P$4") (pinfunction "P$4_P$4") (pintype "bidirectional"))
      (node (ref "U$93") (pin "P$2") (pinfunction "1_P$2") (pintype "bidirectional"))
      (node (ref "U$95") (pin "P$4") (pinfunction "P$4_P$4") (pintype "bidirectional"))
      (node (ref "U$96") (pin "P$4") (pinfunction "P$4_P$4") (pintype "bidirectional"))
      (node (ref "U$97") (pin "P$2") (pinfunction "1_P$2") (pintype "bidirectional"))
      (node (ref "U$99") (pin "P$4") (pinfunction "P$4_P$4") (pintype "bidirectional"))
    )
  )
)
